# 19_2_Coupled_PP0_Top.net
KiCad netlist of a schematic drawn in Altium Designer
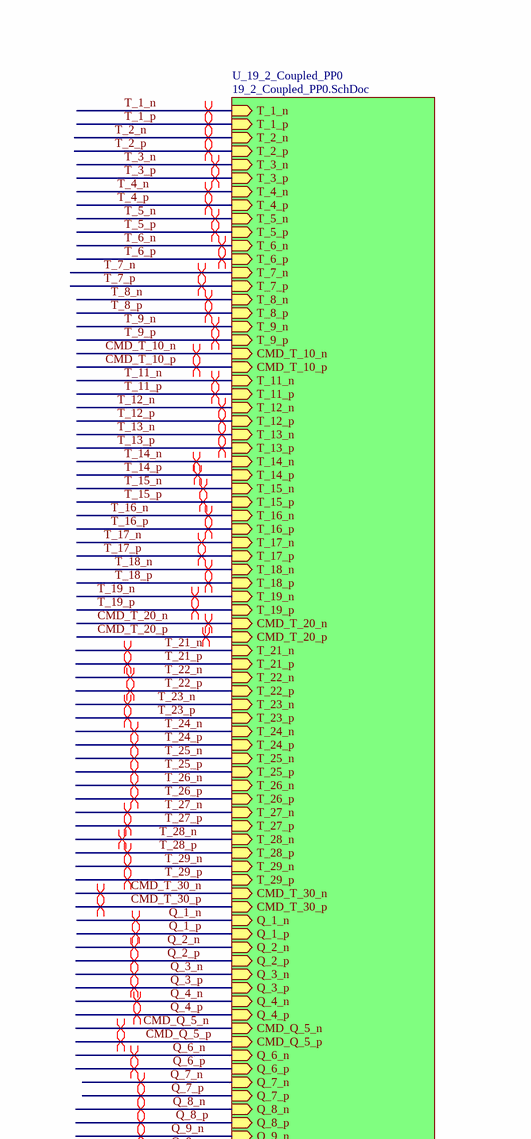
[diagram p0: 19_2_Coupled_PP0_Top.SchDoc, top left]
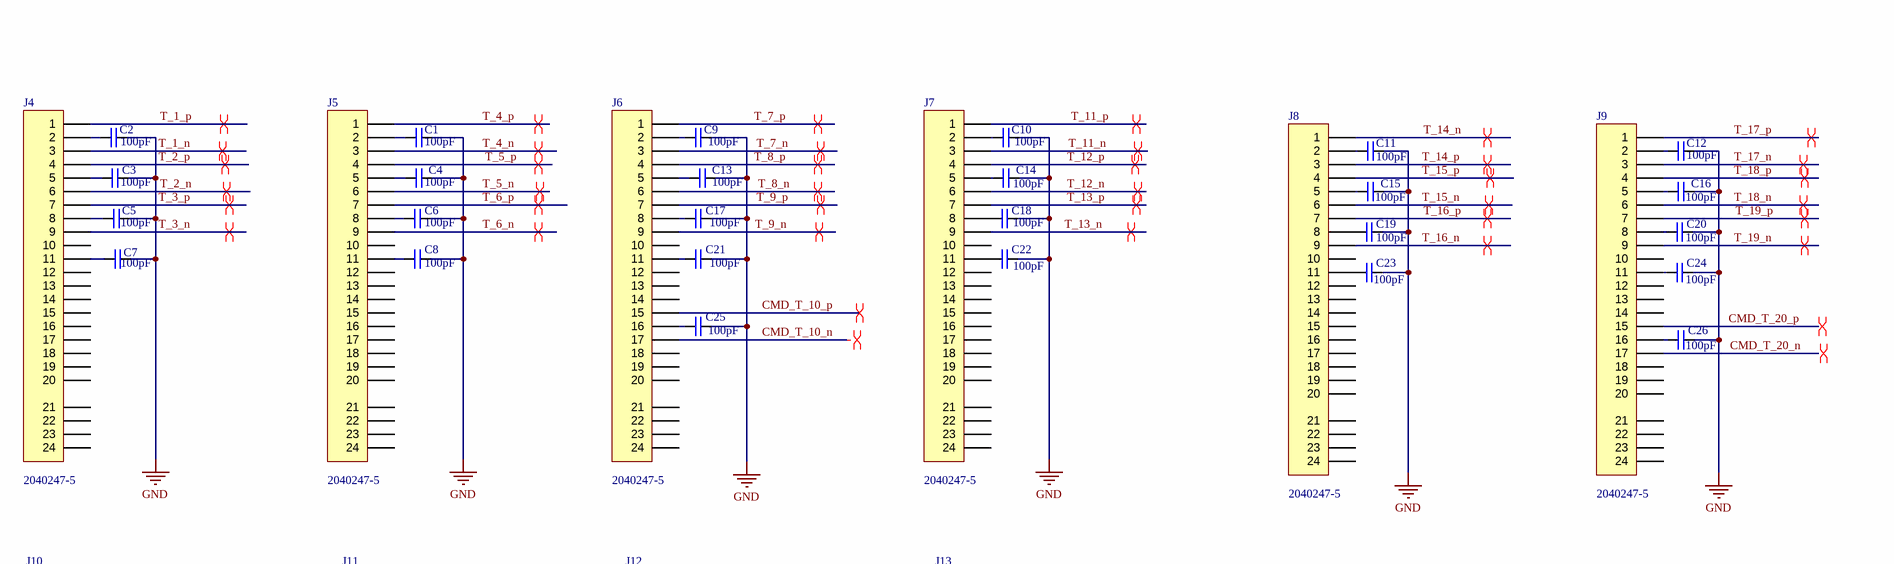
[diagram p1: 19_2_Coupled_PP0_Top.SchDoc, top right]
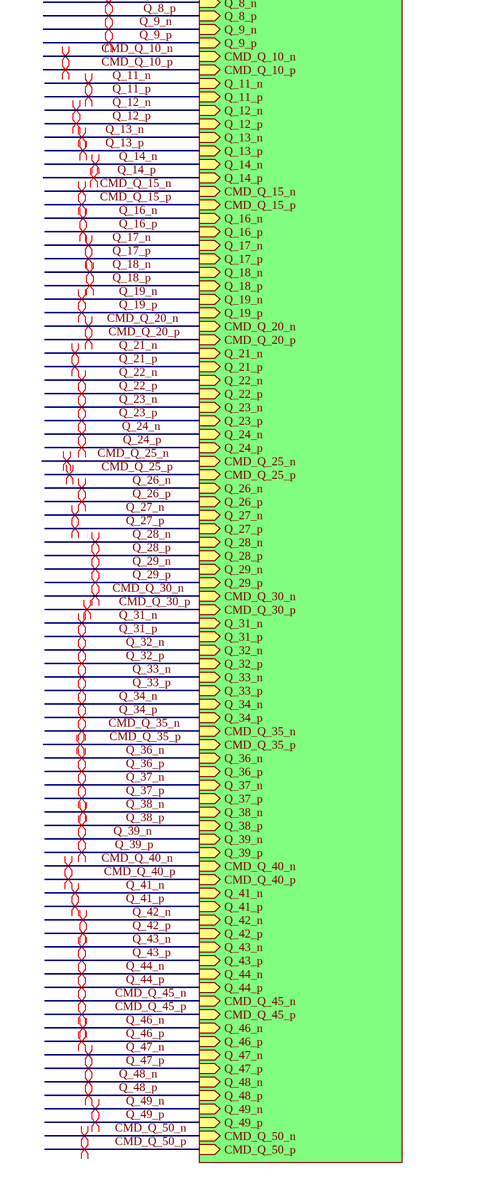
[diagram p2: 19_2_Coupled_PP0_Top.SchDoc, bottom left]
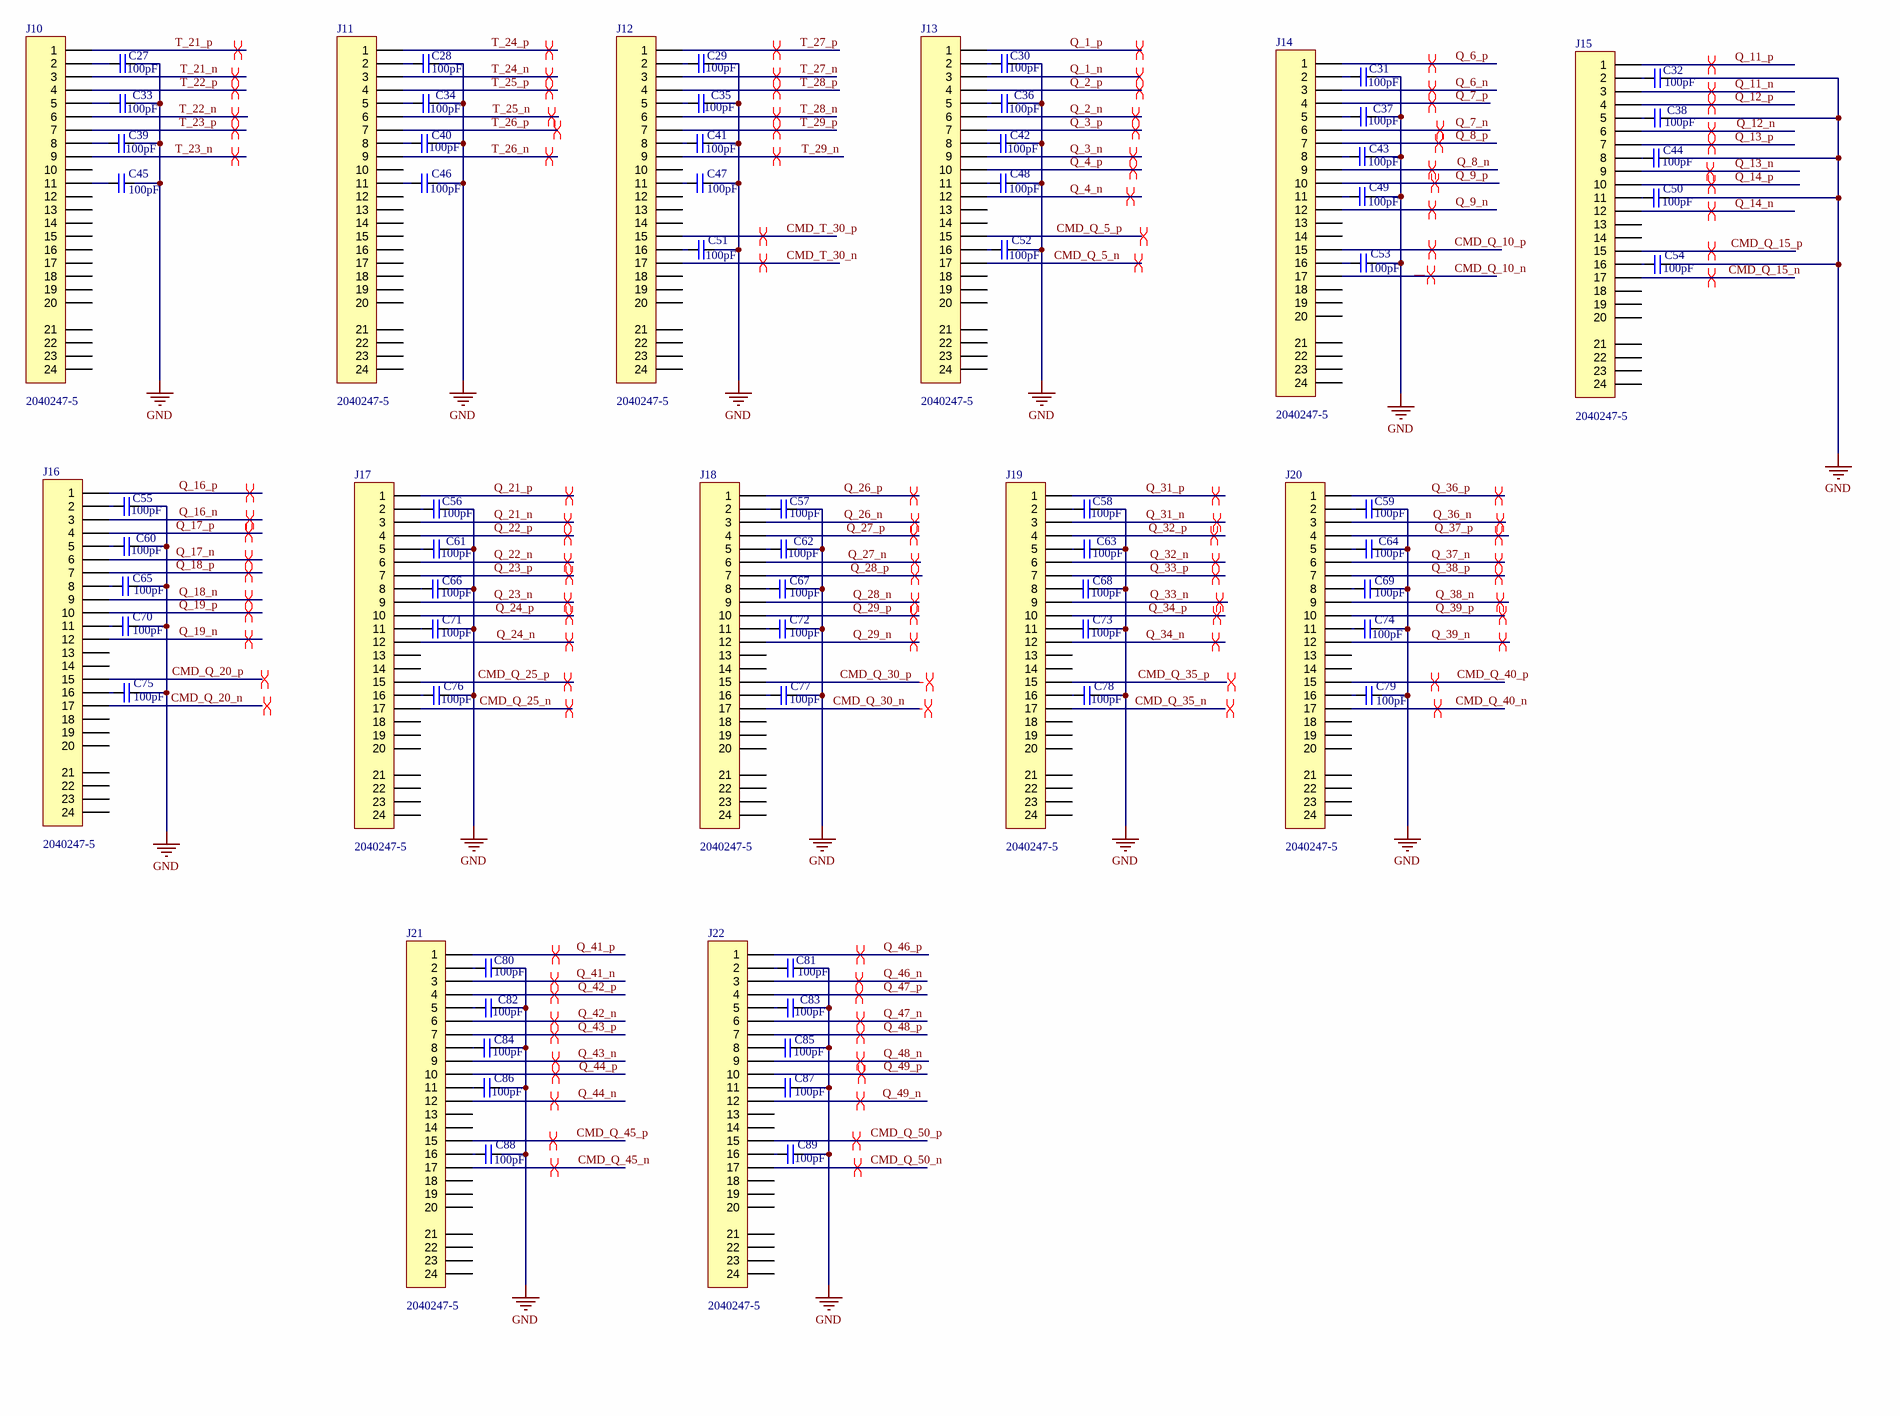
[diagram p3: 19_2_Coupled_PP0_Top.SchDoc, bottom right]

(export (version "E")
  (design (tool "Eeschema 10.0.6"))
  (components
    (comp (ref "C1")
      (value "100pF")
      (footprint "SM0201")
      (description "PPI, 0201N101JW500; CAP. 100pF 50V 5%, SM0201")
      (fields (field (name "MANUFACTURER") "PPI") (field (name "PARTNUMBER") "0201N101JW500"))
      (libsource (lib "yee_sch_lib") (part "C0201N101JW500"))
    )
    (comp (ref "C2")
      (value "100pF")
      (footprint "SM0201")
      (description "PPI, 0201N101JW500; CAP. 100pF 50V 5%, SM0201")
      (fields (field (name "MANUFACTURER") "PPI") (field (name "PARTNUMBER") "0201N101JW500"))
      (libsource (lib "yee_sch_lib") (part "C0201N101JW500"))
    )
    (comp (ref "C3")
      (value "100pF")
      (footprint "SM0201")
      (description "PPI, 0201N101JW500; CAP. 100pF 50V 5%, SM0201")
      (fields (field (name "MANUFACTURER") "PPI") (field (name "PARTNUMBER") "0201N101JW500"))
      (libsource (lib "yee_sch_lib") (part "C0201N101JW500"))
    )
    (comp (ref "C4")
      (value "100pF")
      (footprint "SM0201")
      (description "PPI, 0201N101JW500; CAP. 100pF 50V 5%, SM0201")
      (fields (field (name "MANUFACTURER") "PPI") (field (name "PARTNUMBER") "0201N101JW500"))
      (libsource (lib "yee_sch_lib") (part "C0201N101JW500"))
    )
    (comp (ref "C5")
      (value "100pF")
      (footprint "SM0201")
      (description "PPI, 0201N101JW500; CAP. 100pF 50V 5%, SM0201")
      (fields (field (name "MANUFACTURER") "PPI") (field (name "PARTNUMBER") "0201N101JW500"))
      (libsource (lib "yee_sch_lib") (part "C0201N101JW500"))
    )
    (comp (ref "C6")
      (value "100pF")
      (footprint "SM0201")
      (description "PPI, 0201N101JW500; CAP. 100pF 50V 5%, SM0201")
      (fields (field (name "MANUFACTURER") "PPI") (field (name "PARTNUMBER") "0201N101JW500"))
      (libsource (lib "yee_sch_lib") (part "C0201N101JW500"))
    )
    (comp (ref "C7")
      (value "100pF")
      (footprint "SM0201")
      (description "PPI, 0201N101JW500; CAP. 100pF 50V 5%, SM0201")
      (fields (field (name "MANUFACTURER") "PPI") (field (name "PARTNUMBER") "0201N101JW500"))
      (libsource (lib "yee_sch_lib") (part "C0201N101JW500"))
    )
    (comp (ref "C8")
      (value "100pF")
      (footprint "SM0201")
      (description "PPI, 0201N101JW500; CAP. 100pF 50V 5%, SM0201")
      (fields (field (name "MANUFACTURER") "PPI") (field (name "PARTNUMBER") "0201N101JW500"))
      (libsource (lib "yee_sch_lib") (part "C0201N101JW500"))
    )
    (comp (ref "C9")
      (value "100pF")
      (footprint "SM0201")
      (description "PPI, 0201N101JW500; CAP. 100pF 50V 5%, SM0201")
      (fields (field (name "MANUFACTURER") "PPI") (field (name "PARTNUMBER") "0201N101JW500"))
      (libsource (lib "yee_sch_lib") (part "C0201N101JW500"))
    )
    (comp (ref "C10")
      (value "100pF")
      (footprint "SM0201")
      (description "PPI, 0201N101JW500; CAP. 100pF 50V 5%, SM0201")
      (fields (field (name "MANUFACTURER") "PPI") (field (name "PARTNUMBER") "0201N101JW500"))
      (libsource (lib "yee_sch_lib") (part "C0201N101JW500"))
    )
    (comp (ref "C11")
      (value "100pF")
      (footprint "SM0201")
      (description "PPI, 0201N101JW500; CAP. 100pF 50V 5%, SM0201")
      (fields (field (name "MANUFACTURER") "PPI") (field (name "PARTNUMBER") "0201N101JW500"))
      (libsource (lib "yee_sch_lib") (part "C0201N101JW500"))
    )
    (comp (ref "C12")
      (value "100pF")
      (footprint "SM0201")
      (description "PPI, 0201N101JW500; CAP. 100pF 50V 5%, SM0201")
      (fields (field (name "MANUFACTURER") "PPI") (field (name "PARTNUMBER") "0201N101JW500"))
      (libsource (lib "yee_sch_lib") (part "C0201N101JW500"))
    )
    (comp (ref "C13")
      (value "100pF")
      (footprint "SM0201")
      (description "PPI, 0201N101JW500; CAP. 100pF 50V 5%, SM0201")
      (fields (field (name "MANUFACTURER") "PPI") (field (name "PARTNUMBER") "0201N101JW500"))
      (libsource (lib "yee_sch_lib") (part "C0201N101JW500"))
    )
    (comp (ref "C14")
      (value "100pF")
      (footprint "SM0201")
      (description "PPI, 0201N101JW500; CAP. 100pF 50V 5%, SM0201")
      (fields (field (name "MANUFACTURER") "PPI") (field (name "PARTNUMBER") "0201N101JW500"))
      (libsource (lib "yee_sch_lib") (part "C0201N101JW500"))
    )
    (comp (ref "C15")
      (value "100pF")
      (footprint "SM0201")
      (description "PPI, 0201N101JW500; CAP. 100pF 50V 5%, SM0201")
      (fields (field (name "MANUFACTURER") "PPI") (field (name "PARTNUMBER") "0201N101JW500"))
      (libsource (lib "yee_sch_lib") (part "C0201N101JW500"))
    )
    (comp (ref "C16")
      (value "100pF")
      (footprint "SM0201")
      (description "PPI, 0201N101JW500; CAP. 100pF 50V 5%, SM0201")
      (fields (field (name "MANUFACTURER") "PPI") (field (name "PARTNUMBER") "0201N101JW500"))
      (libsource (lib "yee_sch_lib") (part "C0201N101JW500"))
    )
    (comp (ref "C17")
      (value "100pF")
      (footprint "SM0201")
      (description "PPI, 0201N101JW500; CAP. 100pF 50V 5%, SM0201")
      (fields (field (name "MANUFACTURER") "PPI") (field (name "PARTNUMBER") "0201N101JW500"))
      (libsource (lib "yee_sch_lib") (part "C0201N101JW500"))
    )
    (comp (ref "C18")
      (value "100pF")
      (footprint "SM0201")
      (description "PPI, 0201N101JW500; CAP. 100pF 50V 5%, SM0201")
      (fields (field (name "MANUFACTURER") "PPI") (field (name "PARTNUMBER") "0201N101JW500"))
      (libsource (lib "yee_sch_lib") (part "C0201N101JW500"))
    )
    (comp (ref "C19")
      (value "100pF")
      (footprint "SM0201")
      (description "PPI, 0201N101JW500; CAP. 100pF 50V 5%, SM0201")
      (fields (field (name "MANUFACTURER") "PPI") (field (name "PARTNUMBER") "0201N101JW500"))
      (libsource (lib "yee_sch_lib") (part "C0201N101JW500"))
    )
    (comp (ref "C20")
      (value "100pF")
      (footprint "SM0201")
      (description "PPI, 0201N101JW500; CAP. 100pF 50V 5%, SM0201")
      (fields (field (name "MANUFACTURER") "PPI") (field (name "PARTNUMBER") "0201N101JW500"))
      (libsource (lib "yee_sch_lib") (part "C0201N101JW500"))
    )
    (comp (ref "C21")
      (value "100pF")
      (footprint "SM0201")
      (description "PPI, 0201N101JW500; CAP. 100pF 50V 5%, SM0201")
      (fields (field (name "MANUFACTURER") "PPI") (field (name "PARTNUMBER") "0201N101JW500"))
      (libsource (lib "yee_sch_lib") (part "C0201N101JW500"))
    )
    (comp (ref "C22")
      (value "100pF")
      (footprint "SM0201")
      (description "PPI, 0201N101JW500; CAP. 100pF 50V 5%, SM0201")
      (fields (field (name "MANUFACTURER") "PPI") (field (name "PARTNUMBER") "0201N101JW500"))
      (libsource (lib "yee_sch_lib") (part "C0201N101JW500"))
    )
    (comp (ref "C23")
      (value "100pF")
      (footprint "SM0201")
      (description "PPI, 0201N101JW500; CAP. 100pF 50V 5%, SM0201")
      (fields (field (name "MANUFACTURER") "PPI") (field (name "PARTNUMBER") "0201N101JW500"))
      (libsource (lib "yee_sch_lib") (part "C0201N101JW500"))
    )
    (comp (ref "C24")
      (value "100pF")
      (footprint "SM0201")
      (description "PPI, 0201N101JW500; CAP. 100pF 50V 5%, SM0201")
      (fields (field (name "MANUFACTURER") "PPI") (field (name "PARTNUMBER") "0201N101JW500"))
      (libsource (lib "yee_sch_lib") (part "C0201N101JW500"))
    )
    (comp (ref "C25")
      (value "100pF")
      (footprint "SM0201")
      (description "PPI, 0201N101JW500; CAP. 100pF 50V 5%, SM0201")
      (fields (field (name "MANUFACTURER") "PPI") (field (name "PARTNUMBER") "0201N101JW500"))
      (libsource (lib "yee_sch_lib") (part "C0201N101JW500"))
    )
    (comp (ref "C26")
      (value "100pF")
      (footprint "SM0201")
      (description "PPI, 0201N101JW500; CAP. 100pF 50V 5%, SM0201")
      (fields (field (name "MANUFACTURER") "PPI") (field (name "PARTNUMBER") "0201N101JW500"))
      (libsource (lib "yee_sch_lib") (part "C0201N101JW500"))
    )
    (comp (ref "C27")
      (value "100pF")
      (footprint "SM0201")
      (description "PPI, 0201N101JW500; CAP. 100pF 50V 5%, SM0201")
      (fields (field (name "MANUFACTURER") "PPI") (field (name "PARTNUMBER") "0201N101JW500"))
      (libsource (lib "yee_sch_lib") (part "C0201N101JW500"))
    )
    (comp (ref "C28")
      (value "100pF")
      (footprint "SM0201")
      (description "PPI, 0201N101JW500; CAP. 100pF 50V 5%, SM0201")
      (fields (field (name "MANUFACTURER") "PPI") (field (name "PARTNUMBER") "0201N101JW500"))
      (libsource (lib "yee_sch_lib") (part "C0201N101JW500"))
    )
    (comp (ref "C29")
      (value "100pF")
      (footprint "SM0201")
      (description "PPI, 0201N101JW500; CAP. 100pF 50V 5%, SM0201")
      (fields (field (name "MANUFACTURER") "PPI") (field (name "PARTNUMBER") "0201N101JW500"))
      (libsource (lib "yee_sch_lib") (part "C0201N101JW500"))
    )
    (comp (ref "C30")
      (value "100pF")
      (footprint "SM0201")
      (description "PPI, 0201N101JW500; CAP. 100pF 50V 5%, SM0201")
      (fields (field (name "MANUFACTURER") "PPI") (field (name "PARTNUMBER") "0201N101JW500"))
      (libsource (lib "yee_sch_lib") (part "C0201N101JW500"))
    )
    (comp (ref "C31")
      (value "100pF")
      (footprint "SM0201")
      (description "PPI, 0201N101JW500; CAP. 100pF 50V 5%, SM0201")
      (fields (field (name "MANUFACTURER") "PPI") (field (name "PARTNUMBER") "0201N101JW500"))
      (libsource (lib "yee_sch_lib") (part "C0201N101JW500"))
    )
    (comp (ref "C32")
      (value "100pF")
      (footprint "SM0201")
      (description "PPI, 0201N101JW500; CAP. 100pF 50V 5%, SM0201")
      (fields (field (name "MANUFACTURER") "PPI") (field (name "PARTNUMBER") "0201N101JW500"))
      (libsource (lib "yee_sch_lib") (part "C0201N101JW500"))
    )
    (comp (ref "C33")
      (value "100pF")
      (footprint "SM0201")
      (description "PPI, 0201N101JW500; CAP. 100pF 50V 5%, SM0201")
      (fields (field (name "MANUFACTURER") "PPI") (field (name "PARTNUMBER") "0201N101JW500"))
      (libsource (lib "yee_sch_lib") (part "C0201N101JW500"))
    )
    (comp (ref "C34")
      (value "100pF")
      (footprint "SM0201")
      (description "PPI, 0201N101JW500; CAP. 100pF 50V 5%, SM0201")
      (fields (field (name "MANUFACTURER") "PPI") (field (name "PARTNUMBER") "0201N101JW500"))
      (libsource (lib "yee_sch_lib") (part "C0201N101JW500"))
    )
    (comp (ref "C35")
      (value "100pF")
      (footprint "SM0201")
      (description "PPI, 0201N101JW500; CAP. 100pF 50V 5%, SM0201")
      (fields (field (name "MANUFACTURER") "PPI") (field (name "PARTNUMBER") "0201N101JW500"))
      (libsource (lib "yee_sch_lib") (part "C0201N101JW500"))
    )
    (comp (ref "C36")
      (value "100pF")
      (footprint "SM0201")
      (description "PPI, 0201N101JW500; CAP. 100pF 50V 5%, SM0201")
      (fields (field (name "MANUFACTURER") "PPI") (field (name "PARTNUMBER") "0201N101JW500"))
      (libsource (lib "yee_sch_lib") (part "C0201N101JW500"))
    )
    (comp (ref "C37")
      (value "100pF")
      (footprint "SM0201")
      (description "PPI, 0201N101JW500; CAP. 100pF 50V 5%, SM0201")
      (fields (field (name "MANUFACTURER") "PPI") (field (name "PARTNUMBER") "0201N101JW500"))
      (libsource (lib "yee_sch_lib") (part "C0201N101JW500"))
    )
    (comp (ref "C38")
      (value "100pF")
      (footprint "SM0201")
      (description "PPI, 0201N101JW500; CAP. 100pF 50V 5%, SM0201")
      (fields (field (name "MANUFACTURER") "PPI") (field (name "PARTNUMBER") "0201N101JW500"))
      (libsource (lib "yee_sch_lib") (part "C0201N101JW500"))
    )
    (comp (ref "C39")
      (value "100pF")
      (footprint "SM0201")
      (description "PPI, 0201N101JW500; CAP. 100pF 50V 5%, SM0201")
      (fields (field (name "MANUFACTURER") "PPI") (field (name "PARTNUMBER") "0201N101JW500"))
      (libsource (lib "yee_sch_lib") (part "C0201N101JW500"))
    )
    (comp (ref "C40")
      (value "100pF")
      (footprint "SM0201")
      (description "PPI, 0201N101JW500; CAP. 100pF 50V 5%, SM0201")
      (fields (field (name "MANUFACTURER") "PPI") (field (name "PARTNUMBER") "0201N101JW500"))
      (libsource (lib "yee_sch_lib") (part "C0201N101JW500"))
    )
    (comp (ref "C41")
      (value "100pF")
      (footprint "SM0201")
      (description "PPI, 0201N101JW500; CAP. 100pF 50V 5%, SM0201")
      (fields (field (name "MANUFACTURER") "PPI") (field (name "PARTNUMBER") "0201N101JW500"))
      (libsource (lib "yee_sch_lib") (part "C0201N101JW500"))
    )
    (comp (ref "C42")
      (value "100pF")
      (footprint "SM0201")
      (description "PPI, 0201N101JW500; CAP. 100pF 50V 5%, SM0201")
      (fields (field (name "MANUFACTURER") "PPI") (field (name "PARTNUMBER") "0201N101JW500"))
      (libsource (lib "yee_sch_lib") (part "C0201N101JW500"))
    )
    (comp (ref "C43")
      (value "100pF")
      (footprint "SM0201")
      (description "PPI, 0201N101JW500; CAP. 100pF 50V 5%, SM0201")
      (fields (field (name "MANUFACTURER") "PPI") (field (name "PARTNUMBER") "0201N101JW500"))
      (libsource (lib "yee_sch_lib") (part "C0201N101JW500"))
    )
    (comp (ref "C44")
      (value "100pF")
      (footprint "SM0201")
      (description "PPI, 0201N101JW500; CAP. 100pF 50V 5%, SM0201")
      (fields (field (name "MANUFACTURER") "PPI") (field (name "PARTNUMBER") "0201N101JW500"))
      (libsource (lib "yee_sch_lib") (part "C0201N101JW500"))
    )
    (comp (ref "C45")
      (value "100pF")
      (footprint "SM0201")
      (description "PPI, 0201N101JW500; CAP. 100pF 50V 5%, SM0201")
      (fields (field (name "MANUFACTURER") "PPI") (field (name "PARTNUMBER") "0201N101JW500"))
      (libsource (lib "yee_sch_lib") (part "C0201N101JW500"))
    )
    (comp (ref "C46")
      (value "100pF")
      (footprint "SM0201")
      (description "PPI, 0201N101JW500; CAP. 100pF 50V 5%, SM0201")
      (fields (field (name "MANUFACTURER") "PPI") (field (name "PARTNUMBER") "0201N101JW500"))
      (libsource (lib "yee_sch_lib") (part "C0201N101JW500"))
    )
    (comp (ref "C47")
      (value "100pF")
      (footprint "SM0201")
      (description "PPI, 0201N101JW500; CAP. 100pF 50V 5%, SM0201")
      (fields (field (name "MANUFACTURER") "PPI") (field (name "PARTNUMBER") "0201N101JW500"))
      (libsource (lib "yee_sch_lib") (part "C0201N101JW500"))
    )
    (comp (ref "C48")
      (value "100pF")
      (footprint "SM0201")
      (description "PPI, 0201N101JW500; CAP. 100pF 50V 5%, SM0201")
      (fields (field (name "MANUFACTURER") "PPI") (field (name "PARTNUMBER") "0201N101JW500"))
      (libsource (lib "yee_sch_lib") (part "C0201N101JW500"))
    )
    (comp (ref "C49")
      (value "100pF")
      (footprint "SM0201")
      (description "PPI, 0201N101JW500; CAP. 100pF 50V 5%, SM0201")
      (fields (field (name "MANUFACTURER") "PPI") (field (name "PARTNUMBER") "0201N101JW500"))
      (libsource (lib "yee_sch_lib") (part "C0201N101JW500"))
    )
    (comp (ref "C50")
      (value "100pF")
      (footprint "SM0201")
      (description "PPI, 0201N101JW500; CAP. 100pF 50V 5%, SM0201")
      (fields (field (name "MANUFACTURER") "PPI") (field (name "PARTNUMBER") "0201N101JW500"))
      (libsource (lib "yee_sch_lib") (part "C0201N101JW500"))
    )
    (comp (ref "C51")
      (value "100pF")
      (footprint "SM0201")
      (description "PPI, 0201N101JW500; CAP. 100pF 50V 5%, SM0201")
      (fields (field (name "MANUFACTURER") "PPI") (field (name "PARTNUMBER") "0201N101JW500"))
      (libsource (lib "yee_sch_lib") (part "C0201N101JW500"))
    )
    (comp (ref "C52")
      (value "100pF")
      (footprint "SM0201")
      (description "PPI, 0201N101JW500; CAP. 100pF 50V 5%, SM0201")
      (fields (field (name "MANUFACTURER") "PPI") (field (name "PARTNUMBER") "0201N101JW500"))
      (libsource (lib "yee_sch_lib") (part "C0201N101JW500"))
    )
    (comp (ref "C53")
      (value "100pF")
      (footprint "SM0201")
      (description "PPI, 0201N101JW500; CAP. 100pF 50V 5%, SM0201")
      (fields (field (name "MANUFACTURER") "PPI") (field (name "PARTNUMBER") "0201N101JW500"))
      (libsource (lib "yee_sch_lib") (part "C0201N101JW500"))
    )
    (comp (ref "C54")
      (value "100pF")
      (footprint "SM0201")
      (description "PPI, 0201N101JW500; CAP. 100pF 50V 5%, SM0201")
      (fields (field (name "MANUFACTURER") "PPI") (field (name "PARTNUMBER") "0201N101JW500"))
      (libsource (lib "yee_sch_lib") (part "C0201N101JW500"))
    )
    (comp (ref "C55")
      (value "100pF")
      (footprint "SM0201")
      (description "PPI, 0201N101JW500; CAP. 100pF 50V 5%, SM0201")
      (fields (field (name "MANUFACTURER") "PPI") (field (name "PARTNUMBER") "0201N101JW500"))
      (libsource (lib "yee_sch_lib") (part "C0201N101JW500"))
    )
    (comp (ref "C56")
      (value "100pF")
      (footprint "SM0201")
      (description "PPI, 0201N101JW500; CAP. 100pF 50V 5%, SM0201")
      (fields (field (name "MANUFACTURER") "PPI") (field (name "PARTNUMBER") "0201N101JW500"))
      (libsource (lib "yee_sch_lib") (part "C0201N101JW500"))
    )
    (comp (ref "C57")
      (value "100pF")
      (footprint "SM0201")
      (description "PPI, 0201N101JW500; CAP. 100pF 50V 5%, SM0201")
      (fields (field (name "MANUFACTURER") "PPI") (field (name "PARTNUMBER") "0201N101JW500"))
      (libsource (lib "yee_sch_lib") (part "C0201N101JW500"))
    )
    (comp (ref "C58")
      (value "100pF")
      (footprint "SM0201")
      (description "PPI, 0201N101JW500; CAP. 100pF 50V 5%, SM0201")
      (fields (field (name "MANUFACTURER") "PPI") (field (name "PARTNUMBER") "0201N101JW500"))
      (libsource (lib "yee_sch_lib") (part "C0201N101JW500"))
    )
    (comp (ref "C59")
      (value "100pF")
      (footprint "SM0201")
      (description "PPI, 0201N101JW500; CAP. 100pF 50V 5%, SM0201")
      (fields (field (name "MANUFACTURER") "PPI") (field (name "PARTNUMBER") "0201N101JW500"))
      (libsource (lib "yee_sch_lib") (part "C0201N101JW500"))
    )
    (comp (ref "C60")
      (value "100pF")
      (footprint "SM0201")
      (description "PPI, 0201N101JW500; CAP. 100pF 50V 5%, SM0201")
      (fields (field (name "MANUFACTURER") "PPI") (field (name "PARTNUMBER") "0201N101JW500"))
      (libsource (lib "yee_sch_lib") (part "C0201N101JW500"))
    )
    (comp (ref "C61")
      (value "100pF")
      (footprint "SM0201")
      (description "PPI, 0201N101JW500; CAP. 100pF 50V 5%, SM0201")
      (fields (field (name "MANUFACTURER") "PPI") (field (name "PARTNUMBER") "0201N101JW500"))
      (libsource (lib "yee_sch_lib") (part "C0201N101JW500"))
    )
    (comp (ref "C62")
      (value "100pF")
      (footprint "SM0201")
      (description "PPI, 0201N101JW500; CAP. 100pF 50V 5%, SM0201")
      (fields (field (name "MANUFACTURER") "PPI") (field (name "PARTNUMBER") "0201N101JW500"))
      (libsource (lib "yee_sch_lib") (part "C0201N101JW500"))
    )
    (comp (ref "C63")
      (value "100pF")
      (footprint "SM0201")
      (description "PPI, 0201N101JW500; CAP. 100pF 50V 5%, SM0201")
      (fields (field (name "MANUFACTURER") "PPI") (field (name "PARTNUMBER") "0201N101JW500"))
      (libsource (lib "yee_sch_lib") (part "C0201N101JW500"))
    )
    (comp (ref "C64")
      (value "100pF")
      (footprint "SM0201")
      (description "PPI, 0201N101JW500; CAP. 100pF 50V 5%, SM0201")
      (fields (field (name "MANUFACTURER") "PPI") (field (name "PARTNUMBER") "0201N101JW500"))
      (libsource (lib "yee_sch_lib") (part "C0201N101JW500"))
    )
    (comp (ref "C65")
      (value "100pF")
      (footprint "SM0201")
      (description "PPI, 0201N101JW500; CAP. 100pF 50V 5%, SM0201")
      (fields (field (name "MANUFACTURER") "PPI") (field (name "PARTNUMBER") "0201N101JW500"))
      (libsource (lib "yee_sch_lib") (part "C0201N101JW500"))
    )
    (comp (ref "C66")
      (value "100pF")
      (footprint "SM0201")
      (description "PPI, 0201N101JW500; CAP. 100pF 50V 5%, SM0201")
      (fields (field (name "MANUFACTURER") "PPI") (field (name "PARTNUMBER") "0201N101JW500"))
      (libsource (lib "yee_sch_lib") (part "C0201N101JW500"))
    )
    (comp (ref "C67")
      (value "100pF")
      (footprint "SM0201")
      (description "PPI, 0201N101JW500; CAP. 100pF 50V 5%, SM0201")
      (fields (field (name "MANUFACTURER") "PPI") (field (name "PARTNUMBER") "0201N101JW500"))
      (libsource (lib "yee_sch_lib") (part "C0201N101JW500"))
    )
    (comp (ref "C68")
      (value "100pF")
      (footprint "SM0201")
      (description "PPI, 0201N101JW500; CAP. 100pF 50V 5%, SM0201")
      (fields (field (name "MANUFACTURER") "PPI") (field (name "PARTNUMBER") "0201N101JW500"))
      (libsource (lib "yee_sch_lib") (part "C0201N101JW500"))
    )
    (comp (ref "C69")
      (value "100pF")
      (footprint "SM0201")
      (description "PPI, 0201N101JW500; CAP. 100pF 50V 5%, SM0201")
      (fields (field (name "MANUFACTURER") "PPI") (field (name "PARTNUMBER") "0201N101JW500"))
      (libsource (lib "yee_sch_lib") (part "C0201N101JW500"))
    )
    (comp (ref "C70")
      (value "100pF")
      (footprint "SM0201")
      (description "PPI, 0201N101JW500; CAP. 100pF 50V 5%, SM0201")
      (fields (field (name "MANUFACTURER") "PPI") (field (name "PARTNUMBER") "0201N101JW500"))
      (libsource (lib "yee_sch_lib") (part "C0201N101JW500"))
    )
    (comp (ref "C71")
      (value "100pF")
      (footprint "SM0201")
      (description "PPI, 0201N101JW500; CAP. 100pF 50V 5%, SM0201")
      (fields (field (name "MANUFACTURER") "PPI") (field (name "PARTNUMBER") "0201N101JW500"))
      (libsource (lib "yee_sch_lib") (part "C0201N101JW500"))
    )
    (comp (ref "C72")
      (value "100pF")
      (footprint "SM0201")
      (description "PPI, 0201N101JW500; CAP. 100pF 50V 5%, SM0201")
      (fields (field (name "MANUFACTURER") "PPI") (field (name "PARTNUMBER") "0201N101JW500"))
      (libsource (lib "yee_sch_lib") (part "C0201N101JW500"))
    )
    (comp (ref "C73")
      (value "100pF")
      (footprint "SM0201")
      (description "PPI, 0201N101JW500; CAP. 100pF 50V 5%, SM0201")
      (fields (field (name "MANUFACTURER") "PPI") (field (name "PARTNUMBER") "0201N101JW500"))
      (libsource (lib "yee_sch_lib") (part "C0201N101JW500"))
    )
    (comp (ref "C74")
      (value "100pF")
      (footprint "SM0201")
      (description "PPI, 0201N101JW500; CAP. 100pF 50V 5%, SM0201")
      (fields (field (name "MANUFACTURER") "PPI") (field (name "PARTNUMBER") "0201N101JW500"))
      (libsource (lib "yee_sch_lib") (part "C0201N101JW500"))
    )
    (comp (ref "C75")
      (value "100pF")
      (footprint "SM0201")
      (description "PPI, 0201N101JW500; CAP. 100pF 50V 5%, SM0201")
      (fields (field (name "MANUFACTURER") "PPI") (field (name "PARTNUMBER") "0201N101JW500"))
      (libsource (lib "yee_sch_lib") (part "C0201N101JW500"))
    )
    (comp (ref "C76")
      (value "100pF")
      (footprint "SM0201")
      (description "PPI, 0201N101JW500; CAP. 100pF 50V 5%, SM0201")
      (fields (field (name "MANUFACTURER") "PPI") (field (name "PARTNUMBER") "0201N101JW500"))
      (libsource (lib "yee_sch_lib") (part "C0201N101JW500"))
    )
    (comp (ref "C77")
      (value "100pF")
      (footprint "SM0201")
      (description "PPI, 0201N101JW500; CAP. 100pF 50V 5%, SM0201")
      (fields (field (name "MANUFACTURER") "PPI") (field (name "PARTNUMBER") "0201N101JW500"))
      (libsource (lib "yee_sch_lib") (part "C0201N101JW500"))
    )
    (comp (ref "C78")
      (value "100pF")
      (footprint "SM0201")
      (description "PPI, 0201N101JW500; CAP. 100pF 50V 5%, SM0201")
      (fields (field (name "MANUFACTURER") "PPI") (field (name "PARTNUMBER") "0201N101JW500"))
      (libsource (lib "yee_sch_lib") (part "C0201N101JW500"))
    )
    (comp (ref "C79")
      (value "100pF")
      (footprint "SM0201")
      (description "PPI, 0201N101JW500; CAP. 100pF 50V 5%, SM0201")
      (fields (field (name "MANUFACTURER") "PPI") (field (name "PARTNUMBER") "0201N101JW500"))
      (libsource (lib "yee_sch_lib") (part "C0201N101JW500"))
    )
    (comp (ref "C80")
      (value "100pF")
      (footprint "SM0201")
      (description "PPI, 0201N101JW500; CAP. 100pF 50V 5%, SM0201")
      (fields (field (name "MANUFACTURER") "PPI") (field (name "PARTNUMBER") "0201N101JW500"))
      (libsource (lib "yee_sch_lib") (part "C0201N101JW500"))
    )
    (comp (ref "C81")
      (value "100pF")
      (footprint "SM0201")
      (description "PPI, 0201N101JW500; CAP. 100pF 50V 5%, SM0201")
      (fields (field (name "MANUFACTURER") "PPI") (field (name "PARTNUMBER") "0201N101JW500"))
      (libsource (lib "yee_sch_lib") (part "C0201N101JW500"))
    )
    (comp (ref "C82")
      (value "100pF")
      (footprint "SM0201")
      (description "PPI, 0201N101JW500; CAP. 100pF 50V 5%, SM0201")
      (fields (field (name "MANUFACTURER") "PPI") (field (name "PARTNUMBER") "0201N101JW500"))
      (libsource (lib "yee_sch_lib") (part "C0201N101JW500"))
    )
    (comp (ref "C83")
      (value "100pF")
      (footprint "SM0201")
      (description "PPI, 0201N101JW500; CAP. 100pF 50V 5%, SM0201")
      (fields (field (name "MANUFACTURER") "PPI") (field (name "PARTNUMBER") "0201N101JW500"))
      (libsource (lib "yee_sch_lib") (part "C0201N101JW500"))
    )
    (comp (ref "C84")
      (value "100pF")
      (footprint "SM0201")
      (description "PPI, 0201N101JW500; CAP. 100pF 50V 5%, SM0201")
      (fields (field (name "MANUFACTURER") "PPI") (field (name "PARTNUMBER") "0201N101JW500"))
      (libsource (lib "yee_sch_lib") (part "C0201N101JW500"))
    )
    (comp (ref "C85")
      (value "100pF")
      (footprint "SM0201")
      (description "PPI, 0201N101JW500; CAP. 100pF 50V 5%, SM0201")
      (fields (field (name "MANUFACTURER") "PPI") (field (name "PARTNUMBER") "0201N101JW500"))
      (libsource (lib "yee_sch_lib") (part "C0201N101JW500"))
    )
    (comp (ref "C86")
      (value "100pF")
      (footprint "SM0201")
      (description "PPI, 0201N101JW500; CAP. 100pF 50V 5%, SM0201")
      (fields (field (name "MANUFACTURER") "PPI") (field (name "PARTNUMBER") "0201N101JW500"))
      (libsource (lib "yee_sch_lib") (part "C0201N101JW500"))
    )
    (comp (ref "C87")
      (value "100pF")
      (footprint "SM0201")
      (description "PPI, 0201N101JW500; CAP. 100pF 50V 5%, SM0201")
      (fields (field (name "MANUFACTURER") "PPI") (field (name "PARTNUMBER") "0201N101JW500"))
      (libsource (lib "yee_sch_lib") (part "C0201N101JW500"))
    )
    (comp (ref "C88")
      (value "100pF")
      (footprint "SM0201")
      (description "PPI, 0201N101JW500; CAP. 100pF 50V 5%, SM0201")
      (fields (field (name "MANUFACTURER") "PPI") (field (name "PARTNUMBER") "0201N101JW500"))
      (libsource (lib "yee_sch_lib") (part "C0201N101JW500"))
    )
    (comp (ref "C89")
      (value "100pF")
      (footprint "SM0201")
      (description "PPI, 0201N101JW500; CAP. 100pF 50V 5%, SM0201")
      (fields (field (name "MANUFACTURER") "PPI") (field (name "PARTNUMBER") "0201N101JW500"))
      (libsource (lib "yee_sch_lib") (part "C0201N101JW500"))
    )
    (comp (ref "J4")
      (value "2040247-5")
      (footprint "Tyco_2040247-5")
      (description "Tyco; 2040247-5, Display Port Right Angle SMT, Tyco_2040247-5")
      (fields (field (name "MANUFACTURER") "TYCO") (field (name "MANUFACTURER PART NUMBER") "2040247-5"))
      (libsource (lib "yee_sch_lib") (part "Tyco_2040247-5"))
    )
    (comp (ref "J5")
      (value "2040247-5")
      (footprint "Tyco_2040247-5")
      (description "Tyco; 2040247-5, Display Port Right Angle SMT, Tyco_2040247-5")
      (fields (field (name "MANUFACTURER") "TYCO") (field (name "MANUFACTURER PART NUMBER") "2040247-5"))
      (libsource (lib "yee_sch_lib") (part "Tyco_2040247-5"))
    )
    (comp (ref "J6")
      (value "2040247-5")
      (footprint "Tyco_2040247-5")
      (description "Tyco; 2040247-5, Display Port Right Angle SMT, Tyco_2040247-5")
      (fields (field (name "MANUFACTURER") "TYCO") (field (name "MANUFACTURER PART NUMBER") "2040247-5"))
      (libsource (lib "yee_sch_lib") (part "Tyco_2040247-5"))
    )
    (comp (ref "J7")
      (value "2040247-5")
      (footprint "Tyco_2040247-5")
      (description "Tyco; 2040247-5, Display Port Right Angle SMT, Tyco_2040247-5")
      (fields (field (name "MANUFACTURER") "TYCO") (field (name "MANUFACTURER PART NUMBER") "2040247-5"))
      (libsource (lib "yee_sch_lib") (part "Tyco_2040247-5"))
    )
    (comp (ref "J8")
      (value "2040247-5")
      (footprint "Tyco_2040247-5")
      (description "Tyco; 2040247-5, Display Port Right Angle SMT, Tyco_2040247-5")
      (fields (field (name "MANUFACTURER") "TYCO") (field (name "MANUFACTURER PART NUMBER") "2040247-5"))
      (libsource (lib "yee_sch_lib") (part "Tyco_2040247-5"))
    )
    (comp (ref "J9")
      (value "2040247-5")
      (footprint "Tyco_2040247-5")
      (description "Tyco; 2040247-5, Display Port Right Angle SMT, Tyco_2040247-5")
      (fields (field (name "MANUFACTURER") "TYCO") (field (name "MANUFACTURER PART NUMBER") "2040247-5"))
      (libsource (lib "yee_sch_lib") (part "Tyco_2040247-5"))
    )
    (comp (ref "J10")
      (value "2040247-5")
      (footprint "Tyco_2040247-5")
      (description "Tyco; 2040247-5, Display Port Right Angle SMT, Tyco_2040247-5")
      (fields (field (name "MANUFACTURER") "TYCO") (field (name "MANUFACTURER PART NUMBER") "2040247-5"))
      (libsource (lib "yee_sch_lib") (part "Tyco_2040247-5"))
    )
    (comp (ref "J11")
      (value "2040247-5")
      (footprint "Tyco_2040247-5")
      (description "Tyco; 2040247-5, Display Port Right Angle SMT, Tyco_2040247-5")
      (fields (field (name "MANUFACTURER") "TYCO") (field (name "MANUFACTURER PART NUMBER") "2040247-5"))
      (libsource (lib "yee_sch_lib") (part "Tyco_2040247-5"))
    )
    (comp (ref "J12")
      (value "2040247-5")
      (footprint "Tyco_2040247-5")
      (description "Tyco; 2040247-5, Display Port Right Angle SMT, Tyco_2040247-5")
      (fields (field (name "MANUFACTURER") "TYCO") (field (name "MANUFACTURER PART NUMBER") "2040247-5"))
      (libsource (lib "yee_sch_lib") (part "Tyco_2040247-5"))
    )
    (comp (ref "J13")
      (value "2040247-5")
      (footprint "Tyco_2040247-5")
      (description "Tyco; 2040247-5, Display Port Right Angle SMT, Tyco_2040247-5")
      (fields (field (name "MANUFACTURER") "TYCO") (field (name "MANUFACTURER PART NUMBER") "2040247-5"))
      (libsource (lib "yee_sch_lib") (part "Tyco_2040247-5"))
    )
    (comp (ref "J14")
      (value "2040247-5")
      (footprint "Tyco_2040247-5")
      (description "Tyco; 2040247-5, Display Port Right Angle SMT, Tyco_2040247-5")
      (fields (field (name "MANUFACTURER") "TYCO") (field (name "MANUFACTURER PART NUMBER") "2040247-5"))
      (libsource (lib "yee_sch_lib") (part "Tyco_2040247-5"))
    )
    (comp (ref "J15")
      (value "2040247-5")
      (footprint "Tyco_2040247-5")
      (description "Tyco; 2040247-5, Display Port Right Angle SMT, Tyco_2040247-5")
      (fields (field (name "MANUFACTURER") "TYCO") (field (name "MANUFACTURER PART NUMBER") "2040247-5"))
      (libsource (lib "yee_sch_lib") (part "Tyco_2040247-5"))
    )
    (comp (ref "J16")
      (value "2040247-5")
      (footprint "Tyco_2040247-5")
      (description "Tyco; 2040247-5, Display Port Right Angle SMT, Tyco_2040247-5")
      (fields (field (name "MANUFACTURER") "TYCO") (field (name "MANUFACTURER PART NUMBER") "2040247-5"))
      (libsource (lib "yee_sch_lib") (part "Tyco_2040247-5"))
    )
    (comp (ref "J17")
      (value "2040247-5")
      (footprint "Tyco_2040247-5")
      (description "Tyco; 2040247-5, Display Port Right Angle SMT, Tyco_2040247-5")
      (fields (field (name "MANUFACTURER") "TYCO") (field (name "MANUFACTURER PART NUMBER") "2040247-5"))
      (libsource (lib "yee_sch_lib") (part "Tyco_2040247-5"))
    )
    (comp (ref "J18")
      (value "2040247-5")
      (footprint "Tyco_2040247-5")
      (description "Tyco; 2040247-5, Display Port Right Angle SMT, Tyco_2040247-5")
      (fields (field (name "MANUFACTURER") "TYCO") (field (name "MANUFACTURER PART NUMBER") "2040247-5"))
      (libsource (lib "yee_sch_lib") (part "Tyco_2040247-5"))
    )
    (comp (ref "J19")
      (value "2040247-5")
      (footprint "Tyco_2040247-5")
      (description "Tyco; 2040247-5, Display Port Right Angle SMT, Tyco_2040247-5")
      (fields (field (name "MANUFACTURER") "TYCO") (field (name "MANUFACTURER PART NUMBER") "2040247-5"))
      (libsource (lib "yee_sch_lib") (part "Tyco_2040247-5"))
    )
    (comp (ref "J20")
      (value "2040247-5")
      (footprint "Tyco_2040247-5")
      (description "Tyco; 2040247-5, Display Port Right Angle SMT, Tyco_2040247-5")
      (fields (field (name "MANUFACTURER") "TYCO") (field (name "MANUFACTURER PART NUMBER") "2040247-5"))
      (libsource (lib "yee_sch_lib") (part "Tyco_2040247-5"))
    )
    (comp (ref "J21")
      (value "2040247-5")
      (footprint "Tyco_2040247-5")
      (description "Tyco; 2040247-5, Display Port Right Angle SMT, Tyco_2040247-5")
      (fields (field (name "MANUFACTURER") "TYCO") (field (name "MANUFACTURER PART NUMBER") "2040247-5"))
      (libsource (lib "yee_sch_lib") (part "Tyco_2040247-5"))
    )
    (comp (ref "J22")
      (value "2040247-5")
      (footprint "Tyco_2040247-5")
      (description "Tyco; 2040247-5, Display Port Right Angle SMT, Tyco_2040247-5")
      (fields (field (name "MANUFACTURER") "TYCO") (field (name "MANUFACTURER PART NUMBER") "2040247-5"))
      (libsource (lib "yee_sch_lib") (part "Tyco_2040247-5"))
    )
  )
  (nets
    (net (code "1") (name "/CMD_Q_5_n") (class "Default")
      (node (ref "J13") (pin "17") (pinfunction "17_17") (pintype "passive"))
    )
    (net (code "2") (name "/CMD_Q_5_p") (class "Default")
      (node (ref "J13") (pin "15") (pinfunction "15_15") (pintype "passive"))
    )
    (net (code "3") (name "/CMD_Q_10_n") (class "Default")
      (node (ref "J14") (pin "17") (pinfunction "17_17") (pintype "passive"))
    )
    (net (code "4") (name "/CMD_Q_10_p") (class "Default")
      (node (ref "J14") (pin "15") (pinfunction "15_15") (pintype "passive"))
    )
    (net (code "5") (name "/CMD_Q_15_n") (class "Default")
      (node (ref "J15") (pin "17") (pinfunction "17_17") (pintype "passive"))
    )
    (net (code "6") (name "/CMD_Q_15_p") (class "Default")
      (node (ref "J15") (pin "15") (pinfunction "15_15") (pintype "passive"))
    )
    (net (code "7") (name "/CMD_Q_20_n") (class "Default")
      (node (ref "J16") (pin "17") (pinfunction "17_17") (pintype "passive"))
    )
    (net (code "8") (name "/CMD_Q_20_p") (class "Default")
      (node (ref "J16") (pin "15") (pinfunction "15_15") (pintype "passive"))
    )
    (net (code "9") (name "/CMD_Q_25_n") (class "Default")
      (node (ref "J17") (pin "17") (pinfunction "17_17") (pintype "passive"))
    )
    (net (code "10") (name "/CMD_Q_25_p") (class "Default")
      (node (ref "J17") (pin "15") (pinfunction "15_15") (pintype "passive"))
    )
    (net (code "11") (name "/CMD_Q_30_n") (class "Default")
      (node (ref "J18") (pin "17") (pinfunction "17_17") (pintype "passive"))
    )
    (net (code "12") (name "/CMD_Q_30_p") (class "Default")
      (node (ref "J18") (pin "15") (pinfunction "15_15") (pintype "passive"))
    )
    (net (code "13") (name "/CMD_Q_35_n") (class "Default")
      (node (ref "J19") (pin "17") (pinfunction "17_17") (pintype "passive"))
    )
    (net (code "14") (name "/CMD_Q_35_p") (class "Default")
      (node (ref "J19") (pin "15") (pinfunction "15_15") (pintype "passive"))
    )
    (net (code "15") (name "/CMD_Q_40_n") (class "Default")
      (node (ref "J20") (pin "17") (pinfunction "17_17") (pintype "passive"))
    )
    (net (code "16") (name "/CMD_Q_40_p") (class "Default")
      (node (ref "J20") (pin "15") (pinfunction "15_15") (pintype "passive"))
    )
    (net (code "17") (name "/CMD_Q_45_n") (class "Default")
      (node (ref "J21") (pin "17") (pinfunction "17_17") (pintype "passive"))
    )
    (net (code "18") (name "/CMD_Q_45_p") (class "Default")
      (node (ref "J21") (pin "15") (pinfunction "15_15") (pintype "passive"))
    )
    (net (code "19") (name "/CMD_Q_50_n") (class "Default")
      (node (ref "J22") (pin "17") (pinfunction "17_17") (pintype "passive"))
    )
    (net (code "20") (name "/CMD_Q_50_p") (class "Default")
      (node (ref "J22") (pin "15") (pinfunction "15_15") (pintype "passive"))
    )
    (net (code "21") (name "/CMD_T_10_n") (class "Default")
      (node (ref "J6") (pin "17") (pinfunction "17_17") (pintype "passive"))
    )
    (net (code "22") (name "/CMD_T_10_p") (class "Default")
      (node (ref "J6") (pin "15") (pinfunction "15_15") (pintype "passive"))
    )
    (net (code "23") (name "/CMD_T_20_n") (class "Default")
      (node (ref "J9") (pin "17") (pinfunction "17_17") (pintype "passive"))
    )
    (net (code "24") (name "/CMD_T_20_p") (class "Default")
      (node (ref "J9") (pin "15") (pinfunction "15_15") (pintype "passive"))
    )
    (net (code "25") (name "/CMD_T_30_n") (class "Default")
      (node (ref "J12") (pin "17") (pinfunction "17_17") (pintype "passive"))
    )
    (net (code "26") (name "/CMD_T_30_p") (class "Default")
      (node (ref "J12") (pin "15") (pinfunction "15_15") (pintype "passive"))
    )
    (net (code "27") (name "/Q_1_n") (class "Default")
      (node (ref "J13") (pin "3") (pinfunction "3_3") (pintype "passive"))
    )
    (net (code "28") (name "/Q_1_p") (class "Default")
      (node (ref "J13") (pin "1") (pinfunction "1_1") (pintype "passive"))
    )
    (net (code "29") (name "/Q_2_n") (class "Default")
      (node (ref "J13") (pin "6") (pinfunction "6_6") (pintype "passive"))
    )
    (net (code "30") (name "/Q_2_p") (class "Default")
      (node (ref "J13") (pin "4") (pinfunction "4_4") (pintype "passive"))
    )
    (net (code "31") (name "/Q_3_n") (class "Default")
      (node (ref "J13") (pin "9") (pinfunction "9_9") (pintype "passive"))
    )
    (net (code "32") (name "/Q_3_p") (class "Default")
      (node (ref "J13") (pin "7") (pinfunction "7_7") (pintype "passive"))
    )
    (net (code "33") (name "/Q_4_n") (class "Default")
      (node (ref "J13") (pin "12") (pinfunction "12_12") (pintype "passive"))
    )
    (net (code "34") (name "/Q_4_p") (class "Default")
      (node (ref "J13") (pin "10") (pinfunction "10_10") (pintype "passive"))
    )
    (net (code "35") (name "/Q_6_n") (class "Default")
      (node (ref "J14") (pin "3") (pinfunction "3_3") (pintype "passive"))
    )
    (net (code "36") (name "/Q_6_p") (class "Default")
      (node (ref "J14") (pin "1") (pinfunction "1_1") (pintype "passive"))
    )
    (net (code "37") (name "/Q_7_n") (class "Default")
      (node (ref "J14") (pin "6") (pinfunction "6_6") (pintype "passive"))
    )
    (net (code "38") (name "/Q_7_p") (class "Default")
      (node (ref "J14") (pin "4") (pinfunction "4_4") (pintype "passive"))
    )
    (net (code "39") (name "/Q_8_n") (class "Default")
      (node (ref "J14") (pin "9") (pinfunction "9_9") (pintype "passive"))
    )
    (net (code "40") (name "/Q_8_p") (class "Default")
      (node (ref "J14") (pin "7") (pinfunction "7_7") (pintype "passive"))
    )
    (net (code "41") (name "/Q_9_n") (class "Default")
      (node (ref "J14") (pin "12") (pinfunction "12_12") (pintype "passive"))
    )
    (net (code "42") (name "/Q_9_p") (class "Default")
      (node (ref "J14") (pin "10") (pinfunction "10_10") (pintype "passive"))
    )
    (net (code "43") (name "/Q_11_n") (class "Default")
      (node (ref "J15") (pin "3") (pinfunction "3_3") (pintype "passive"))
    )
    (net (code "44") (name "/Q_11_p") (class "Default")
      (node (ref "J15") (pin "1") (pinfunction "1_1") (pintype "passive"))
    )
    (net (code "45") (name "/Q_12_n") (class "Default")
      (node (ref "J15") (pin "6") (pinfunction "6_6") (pintype "passive"))
    )
    (net (code "46") (name "/Q_12_p") (class "Default")
      (node (ref "J15") (pin "4") (pinfunction "4_4") (pintype "passive"))
    )
    (net (code "47") (name "/Q_13_n") (class "Default")
      (node (ref "J15") (pin "9") (pinfunction "9_9") (pintype "passive"))
    )
    (net (code "48") (name "/Q_13_p") (class "Default")
      (node (ref "J15") (pin "7") (pinfunction "7_7") (pintype "passive"))
    )
    (net (code "49") (name "/Q_14_n") (class "Default")
      (node (ref "J15") (pin "12") (pinfunction "12_12") (pintype "passive"))
    )
    (net (code "50") (name "/Q_14_p") (class "Default")
      (node (ref "J15") (pin "10") (pinfunction "10_10") (pintype "passive"))
    )
    (net (code "51") (name "/Q_16_n") (class "Default")
      (node (ref "J16") (pin "3") (pinfunction "3_3") (pintype "passive"))
    )
    (net (code "52") (name "/Q_16_p") (class "Default")
      (node (ref "J16") (pin "1") (pinfunction "1_1") (pintype "passive"))
    )
    (net (code "53") (name "/Q_17_n") (class "Default")
      (node (ref "J16") (pin "6") (pinfunction "6_6") (pintype "passive"))
    )
    (net (code "54") (name "/Q_17_p") (class "Default")
      (node (ref "J16") (pin "4") (pinfunction "4_4") (pintype "passive"))
    )
    (net (code "55") (name "/Q_18_n") (class "Default")
      (node (ref "J16") (pin "9") (pinfunction "9_9") (pintype "passive"))
    )
    (net (code "56") (name "/Q_18_p") (class "Default")
      (node (ref "J16") (pin "7") (pinfunction "7_7") (pintype "passive"))
    )
    (net (code "57") (name "/Q_19_n") (class "Default")
      (node (ref "J16") (pin "12") (pinfunction "12_12") (pintype "passive"))
    )
    (net (code "58") (name "/Q_19_p") (class "Default")
      (node (ref "J16") (pin "10") (pinfunction "10_10") (pintype "passive"))
    )
    (net (code "59") (name "/Q_21_n") (class "Default")
      (node (ref "J17") (pin "3") (pinfunction "3_3") (pintype "passive"))
    )
    (net (code "60") (name "/Q_21_p") (class "Default")
      (node (ref "J17") (pin "1") (pinfunction "1_1") (pintype "passive"))
    )
    (net (code "61") (name "/Q_22_n") (class "Default")
      (node (ref "J17") (pin "6") (pinfunction "6_6") (pintype "passive"))
    )
    (net (code "62") (name "/Q_22_p") (class "Default")
      (node (ref "J17") (pin "4") (pinfunction "4_4") (pintype "passive"))
    )
    (net (code "63") (name "/Q_23_n") (class "Default")
      (node (ref "J17") (pin "9") (pinfunction "9_9") (pintype "passive"))
    )
    (net (code "64") (name "/Q_23_p") (class "Default")
      (node (ref "J17") (pin "7") (pinfunction "7_7") (pintype "passive"))
    )
    (net (code "65") (name "/Q_24_n") (class "Default")
      (node (ref "J17") (pin "12") (pinfunction "12_12") (pintype "passive"))
    )
    (net (code "66") (name "/Q_24_p") (class "Default")
      (node (ref "J17") (pin "10") (pinfunction "10_10") (pintype "passive"))
    )
    (net (code "67") (name "/Q_26_n") (class "Default")
      (node (ref "J18") (pin "3") (pinfunction "3_3") (pintype "passive"))
    )
    (net (code "68") (name "/Q_26_p") (class "Default")
      (node (ref "J18") (pin "1") (pinfunction "1_1") (pintype "passive"))
    )
    (net (code "69") (name "/Q_27_n") (class "Default")
      (node (ref "J18") (pin "6") (pinfunction "6_6") (pintype "passive"))
    )
    (net (code "70") (name "/Q_27_p") (class "Default")
      (node (ref "J18") (pin "4") (pinfunction "4_4") (pintype "passive"))
    )
    (net (code "71") (name "/Q_28_n") (class "Default")
      (node (ref "J18") (pin "9") (pinfunction "9_9") (pintype "passive"))
    )
    (net (code "72") (name "/Q_28_p") (class "Default")
      (node (ref "J18") (pin "7") (pinfunction "7_7") (pintype "passive"))
    )
    (net (code "73") (name "/Q_29_n") (class "Default")
      (node (ref "J18") (pin "12") (pinfunction "12_12") (pintype "passive"))
    )
    (net (code "74") (name "/Q_29_p") (class "Default")
      (node (ref "J18") (pin "10") (pinfunction "10_10") (pintype "passive"))
    )
    (net (code "75") (name "/Q_31_n") (class "Default")
      (node (ref "J19") (pin "3") (pinfunction "3_3") (pintype "passive"))
    )
    (net (code "76") (name "/Q_31_p") (class "Default")
      (node (ref "J19") (pin "1") (pinfunction "1_1") (pintype "passive"))
    )
    (net (code "77") (name "/Q_32_n") (class "Default")
      (node (ref "J19") (pin "6") (pinfunction "6_6") (pintype "passive"))
    )
    (net (code "78") (name "/Q_32_p") (class "Default")
      (node (ref "J19") (pin "4") (pinfunction "4_4") (pintype "passive"))
    )
    (net (code "79") (name "/Q_33_n") (class "Default")
      (node (ref "J19") (pin "9") (pinfunction "9_9") (pintype "passive"))
    )
    (net (code "80") (name "/Q_33_p") (class "Default")
      (node (ref "J19") (pin "7") (pinfunction "7_7") (pintype "passive"))
    )
    (net (code "81") (name "/Q_34_n") (class "Default")
      (node (ref "J19") (pin "12") (pinfunction "12_12") (pintype "passive"))
    )
    (net (code "82") (name "/Q_34_p") (class "Default")
      (node (ref "J19") (pin "10") (pinfunction "10_10") (pintype "passive"))
    )
    (net (code "83") (name "/Q_36_n") (class "Default")
      (node (ref "J20") (pin "3") (pinfunction "3_3") (pintype "passive"))
    )
    (net (code "84") (name "/Q_36_p") (class "Default")
      (node (ref "J20") (pin "1") (pinfunction "1_1") (pintype "passive"))
    )
    (net (code "85") (name "/Q_37_n") (class "Default")
      (node (ref "J20") (pin "6") (pinfunction "6_6") (pintype "passive"))
    )
    (net (code "86") (name "/Q_37_p") (class "Default")
      (node (ref "J20") (pin "4") (pinfunction "4_4") (pintype "passive"))
    )
    (net (code "87") (name "/Q_38_n") (class "Default")
      (node (ref "J20") (pin "9") (pinfunction "9_9") (pintype "passive"))
    )
    (net (code "88") (name "/Q_38_p") (class "Default")
      (node (ref "J20") (pin "7") (pinfunction "7_7") (pintype "passive"))
    )
    (net (code "89") (name "/Q_39_n") (class "Default")
      (node (ref "J20") (pin "12") (pinfunction "12_12") (pintype "passive"))
    )
    (net (code "90") (name "/Q_39_p") (class "Default")
      (node (ref "J20") (pin "10") (pinfunction "10_10") (pintype "passive"))
    )
    (net (code "91") (name "/Q_41_n") (class "Default")
      (node (ref "J21") (pin "3") (pinfunction "3_3") (pintype "passive"))
    )
    (net (code "92") (name "/Q_41_p") (class "Default")
      (node (ref "J21") (pin "1") (pinfunction "1_1") (pintype "passive"))
    )
    (net (code "93") (name "/Q_42_n") (class "Default")
      (node (ref "J21") (pin "6") (pinfunction "6_6") (pintype "passive"))
    )
    (net (code "94") (name "/Q_42_p") (class "Default")
      (node (ref "J21") (pin "4") (pinfunction "4_4") (pintype "passive"))
    )
    (net (code "95") (name "/Q_43_n") (class "Default")
      (node (ref "J21") (pin "9") (pinfunction "9_9") (pintype "passive"))
    )
    (net (code "96") (name "/Q_43_p") (class "Default")
      (node (ref "J21") (pin "7") (pinfunction "7_7") (pintype "passive"))
    )
    (net (code "97") (name "/Q_44_n") (class "Default")
      (node (ref "J21") (pin "12") (pinfunction "12_12") (pintype "passive"))
    )
    (net (code "98") (name "/Q_44_p") (class "Default")
      (node (ref "J21") (pin "10") (pinfunction "10_10") (pintype "passive"))
    )
    (net (code "99") (name "/Q_46_n") (class "Default")
      (node (ref "J22") (pin "3") (pinfunction "3_3") (pintype "passive"))
    )
    (net (code "100") (name "/Q_46_p") (class "Default")
      (node (ref "J22") (pin "1") (pinfunction "1_1") (pintype "passive"))
    )
    (net (code "101") (name "/Q_47_n") (class "Default")
      (node (ref "J22") (pin "6") (pinfunction "6_6") (pintype "passive"))
    )
    (net (code "102") (name "/Q_47_p") (class "Default")
      (node (ref "J22") (pin "4") (pinfunction "4_4") (pintype "passive"))
    )
    (net (code "103") (name "/Q_48_n") (class "Default")
      (node (ref "J22") (pin "9") (pinfunction "9_9") (pintype "passive"))
    )
    (net (code "104") (name "/Q_48_p") (class "Default")
      (node (ref "J22") (pin "7") (pinfunction "7_7") (pintype "passive"))
    )
    (net (code "105") (name "/Q_49_n") (class "Default")
      (node (ref "J22") (pin "12") (pinfunction "12_12") (pintype "passive"))
    )
    (net (code "106") (name "/Q_49_p") (class "Default")
      (node (ref "J22") (pin "10") (pinfunction "10_10") (pintype "passive"))
    )
    (net (code "107") (name "/T_1_n") (class "Default")
      (node (ref "J4") (pin "3") (pinfunction "3_3") (pintype "passive"))
    )
    (net (code "108") (name "/T_1_p") (class "Default")
      (node (ref "J4") (pin "1") (pinfunction "1_1") (pintype "passive"))
    )
    (net (code "109") (name "/T_2_n") (class "Default")
      (node (ref "J4") (pin "6") (pinfunction "6_6") (pintype "passive"))
    )
    (net (code "110") (name "/T_2_p") (class "Default")
      (node (ref "J4") (pin "4") (pinfunction "4_4") (pintype "passive"))
    )
    (net (code "111") (name "/T_3_n") (class "Default")
      (node (ref "J4") (pin "9") (pinfunction "9_9") (pintype "passive"))
    )
    (net (code "112") (name "/T_3_p") (class "Default")
      (node (ref "J4") (pin "7") (pinfunction "7_7") (pintype "passive"))
    )
    (net (code "113") (name "/T_4_n") (class "Default")
      (node (ref "J5") (pin "3") (pinfunction "3_3") (pintype "passive"))
    )
    (net (code "114") (name "/T_4_p") (class "Default")
      (node (ref "J5") (pin "1") (pinfunction "1_1") (pintype "passive"))
    )
    (net (code "115") (name "/T_5_n") (class "Default")
      (node (ref "J5") (pin "6") (pinfunction "6_6") (pintype "passive"))
    )
    (net (code "116") (name "/T_5_p") (class "Default")
      (node (ref "J5") (pin "4") (pinfunction "4_4") (pintype "passive"))
    )
    (net (code "117") (name "/T_6_n") (class "Default")
      (node (ref "J5") (pin "9") (pinfunction "9_9") (pintype "passive"))
    )
    (net (code "118") (name "/T_6_p") (class "Default")
      (node (ref "J5") (pin "7") (pinfunction "7_7") (pintype "passive"))
    )
    (net (code "119") (name "/T_7_n") (class "Default")
      (node (ref "J6") (pin "3") (pinfunction "3_3") (pintype "passive"))
    )
    (net (code "120") (name "/T_7_p") (class "Default")
      (node (ref "J6") (pin "1") (pinfunction "1_1") (pintype "passive"))
    )
    (net (code "121") (name "/T_8_n") (class "Default")
      (node (ref "J6") (pin "6") (pinfunction "6_6") (pintype "passive"))
    )
    (net (code "122") (name "/T_8_p") (class "Default")
      (node (ref "J6") (pin "4") (pinfunction "4_4") (pintype "passive"))
    )
    (net (code "123") (name "/T_9_n") (class "Default")
      (node (ref "J6") (pin "9") (pinfunction "9_9") (pintype "passive"))
    )
    (net (code "124") (name "/T_9_p") (class "Default")
      (node (ref "J6") (pin "7") (pinfunction "7_7") (pintype "passive"))
    )
    (net (code "125") (name "/T_11_n") (class "Default")
      (node (ref "J7") (pin "3") (pinfunction "3_3") (pintype "passive"))
    )
    (net (code "126") (name "/T_11_p") (class "Default")
      (node (ref "J7") (pin "1") (pinfunction "1_1") (pintype "passive"))
    )
    (net (code "127") (name "/T_12_n") (class "Default")
      (node (ref "J7") (pin "6") (pinfunction "6_6") (pintype "passive"))
    )
    (net (code "128") (name "/T_12_p") (class "Default")
      (node (ref "J7") (pin "4") (pinfunction "4_4") (pintype "passive"))
    )
    (net (code "129") (name "/T_13_n") (class "Default")
      (node (ref "J7") (pin "9") (pinfunction "9_9") (pintype "passive"))
    )
    (net (code "130") (name "/T_13_p") (class "Default")
      (node (ref "J7") (pin "7") (pinfunction "7_7") (pintype "passive"))
    )
    (net (code "131") (name "/T_14_n") (class "Default")
      (node (ref "J8") (pin "1") (pinfunction "1_1") (pintype "passive"))
    )
    (net (code "132") (name "/T_14_p") (class "Default")
      (node (ref "J8") (pin "3") (pinfunction "3_3") (pintype "passive"))
    )
    (net (code "133") (name "/T_15_n") (class "Default")
      (node (ref "J8") (pin "6") (pinfunction "6_6") (pintype "passive"))
    )
    (net (code "134") (name "/T_15_p") (class "Default")
      (node (ref "J8") (pin "4") (pinfunction "4_4") (pintype "passive"))
    )
    (net (code "135") (name "/T_16_n") (class "Default")
      (node (ref "J8") (pin "9") (pinfunction "9_9") (pintype "passive"))
    )
    (net (code "136") (name "/T_16_p") (class "Default")
      (node (ref "J8") (pin "7") (pinfunction "7_7") (pintype "passive"))
    )
    (net (code "137") (name "/T_17_n") (class "Default")
      (node (ref "J9") (pin "3") (pinfunction "3_3") (pintype "passive"))
    )
    (net (code "138") (name "/T_17_p") (class "Default")
      (node (ref "J9") (pin "1") (pinfunction "1_1") (pintype "passive"))
    )
    (net (code "139") (name "/T_18_n") (class "Default")
      (node (ref "J9") (pin "6") (pinfunction "6_6") (pintype "passive"))
    )
    (net (code "140") (name "/T_18_p") (class "Default")
      (node (ref "J9") (pin "4") (pinfunction "4_4") (pintype "passive"))
    )
    (net (code "141") (name "/T_19_n") (class "Default")
      (node (ref "J9") (pin "9") (pinfunction "9_9") (pintype "passive"))
    )
    (net (code "142") (name "/T_19_p") (class "Default")
      (node (ref "J9") (pin "7") (pinfunction "7_7") (pintype "passive"))
    )
    (net (code "143") (name "/T_21_n") (class "Default")
      (node (ref "J10") (pin "3") (pinfunction "3_3") (pintype "passive"))
    )
    (net (code "144") (name "/T_21_p") (class "Default")
      (node (ref "J10") (pin "1") (pinfunction "1_1") (pintype "passive"))
    )
    (net (code "145") (name "/T_22_n") (class "Default")
      (node (ref "J10") (pin "6") (pinfunction "6_6") (pintype "passive"))
    )
    (net (code "146") (name "/T_22_p") (class "Default")
      (node (ref "J10") (pin "4") (pinfunction "4_4") (pintype "passive"))
    )
    (net (code "147") (name "/T_23_n") (class "Default")
      (node (ref "J10") (pin "9") (pinfunction "9_9") (pintype "passive"))
    )
    (net (code "148") (name "/T_23_p") (class "Default")
      (node (ref "J10") (pin "7") (pinfunction "7_7") (pintype "passive"))
    )
    (net (code "149") (name "/T_24_n") (class "Default")
      (node (ref "J11") (pin "3") (pinfunction "3_3") (pintype "passive"))
    )
    (net (code "150") (name "/T_24_p") (class "Default")
      (node (ref "J11") (pin "1") (pinfunction "1_1") (pintype "passive"))
    )
    (net (code "151") (name "/T_25_n") (class "Default")
      (node (ref "J11") (pin "6") (pinfunction "6_6") (pintype "passive"))
    )
    (net (code "152") (name "/T_25_p") (class "Default")
      (node (ref "J11") (pin "4") (pinfunction "4_4") (pintype "passive"))
    )
    (net (code "153") (name "/T_26_n") (class "Default")
      (node (ref "J11") (pin "9") (pinfunction "9_9") (pintype "passive"))
    )
    (net (code "154") (name "/T_26_p") (class "Default")
      (node (ref "J11") (pin "7") (pinfunction "7_7") (pintype "passive"))
    )
    (net (code "155") (name "/T_27_n") (class "Default")
      (node (ref "J12") (pin "3") (pinfunction "3_3") (pintype "passive"))
    )
    (net (code "156") (name "/T_27_p") (class "Default")
      (node (ref "J12") (pin "1") (pinfunction "1_1") (pintype "passive"))
    )
    (net (code "157") (name "/T_28_n") (class "Default")
      (node (ref "J12") (pin "6") (pinfunction "6_6") (pintype "passive"))
    )
    (net (code "158") (name "/T_28_p") (class "Default")
      (node (ref "J12") (pin "4") (pinfunction "4_4") (pintype "passive"))
    )
    (net (code "159") (name "/T_29_n") (class "Default")
      (node (ref "J12") (pin "9") (pinfunction "9_9") (pintype "passive"))
    )
    (net (code "160") (name "/T_29_p") (class "Default")
      (node (ref "J12") (pin "7") (pinfunction "7_7") (pintype "passive"))
    )
    (net (code "161") (name "GND") (class "Default")
      (node (ref "C1") (pin "1") (pinfunction "1_1") (pintype "passive"))
      (node (ref "C10") (pin "1") (pinfunction "1_1") (pintype "passive"))
      (node (ref "C11") (pin "1") (pinfunction "1_1") (pintype "passive"))
      (node (ref "C12") (pin "1") (pinfunction "1_1") (pintype "passive"))
      (node (ref "C13") (pin "1") (pinfunction "1_1") (pintype "passive"))
      (node (ref "C14") (pin "1") (pinfunction "1_1") (pintype "passive"))
      (node (ref "C15") (pin "1") (pinfunction "1_1") (pintype "passive"))
      (node (ref "C16") (pin "1") (pinfunction "1_1") (pintype "passive"))
      (node (ref "C17") (pin "1") (pinfunction "1_1") (pintype "passive"))
      (node (ref "C18") (pin "1") (pinfunction "1_1") (pintype "passive"))
      (node (ref "C19") (pin "1") (pinfunction "1_1") (pintype "passive"))
      (node (ref "C2") (pin "1") (pinfunction "1_1") (pintype "passive"))
      (node (ref "C20") (pin "1") (pinfunction "1_1") (pintype "passive"))
      (node (ref "C21") (pin "1") (pinfunction "1_1") (pintype "passive"))
      (node (ref "C22") (pin "1") (pinfunction "1_1") (pintype "passive"))
      (node (ref "C23") (pin "1") (pinfunction "1_1") (pintype "passive"))
      (node (ref "C24") (pin "1") (pinfunction "1_1") (pintype "passive"))
      (node (ref "C25") (pin "1") (pinfunction "1_1") (pintype "passive"))
      (node (ref "C26") (pin "1") (pinfunction "1_1") (pintype "passive"))
      (node (ref "C27") (pin "1") (pinfunction "1_1") (pintype "passive"))
      (node (ref "C28") (pin "1") (pinfunction "1_1") (pintype "passive"))
      (node (ref "C29") (pin "1") (pinfunction "1_1") (pintype "passive"))
      (node (ref "C3") (pin "1") (pinfunction "1_1") (pintype "passive"))
      (node (ref "C30") (pin "1") (pinfunction "1_1") (pintype "passive"))
      (node (ref "C31") (pin "1") (pinfunction "1_1") (pintype "passive"))
      (node (ref "C32") (pin "1") (pinfunction "1_1") (pintype "passive"))
      (node (ref "C33") (pin "1") (pinfunction "1_1") (pintype "passive"))
      (node (ref "C34") (pin "1") (pinfunction "1_1") (pintype "passive"))
      (node (ref "C35") (pin "1") (pinfunction "1_1") (pintype "passive"))
      (node (ref "C36") (pin "1") (pinfunction "1_1") (pintype "passive"))
      (node (ref "C37") (pin "1") (pinfunction "1_1") (pintype "passive"))
      (node (ref "C38") (pin "1") (pinfunction "1_1") (pintype "passive"))
      (node (ref "C39") (pin "1") (pinfunction "1_1") (pintype "passive"))
      (node (ref "C4") (pin "1") (pinfunction "1_1") (pintype "passive"))
      (node (ref "C40") (pin "1") (pinfunction "1_1") (pintype "passive"))
      (node (ref "C41") (pin "1") (pinfunction "1_1") (pintype "passive"))
      (node (ref "C42") (pin "1") (pinfunction "1_1") (pintype "passive"))
      (node (ref "C43") (pin "1") (pinfunction "1_1") (pintype "passive"))
      (node (ref "C44") (pin "1") (pinfunction "1_1") (pintype "passive"))
      (node (ref "C45") (pin "1") (pinfunction "1_1") (pintype "passive"))
      (node (ref "C46") (pin "1") (pinfunction "1_1") (pintype "passive"))
      (node (ref "C47") (pin "1") (pinfunction "1_1") (pintype "passive"))
      (node (ref "C48") (pin "1") (pinfunction "1_1") (pintype "passive"))
      (node (ref "C49") (pin "1") (pinfunction "1_1") (pintype "passive"))
      (node (ref "C5") (pin "1") (pinfunction "1_1") (pintype "passive"))
      (node (ref "C50") (pin "1") (pinfunction "1_1") (pintype "passive"))
      (node (ref "C51") (pin "1") (pinfunction "1_1") (pintype "passive"))
      (node (ref "C52") (pin "1") (pinfunction "1_1") (pintype "passive"))
      (node (ref "C53") (pin "1") (pinfunction "1_1") (pintype "passive"))
      (node (ref "C54") (pin "1") (pinfunction "1_1") (pintype "passive"))
      (node (ref "C55") (pin "1") (pinfunction "1_1") (pintype "passive"))
      (node (ref "C56") (pin "1") (pinfunction "1_1") (pintype "passive"))
      (node (ref "C57") (pin "1") (pinfunction "1_1") (pintype "passive"))
      (node (ref "C58") (pin "1") (pinfunction "1_1") (pintype "passive"))
      (node (ref "C59") (pin "1") (pinfunction "1_1") (pintype "passive"))
      (node (ref "C6") (pin "1") (pinfunction "1_1") (pintype "passive"))
      (node (ref "C60") (pin "1") (pinfunction "1_1") (pintype "passive"))
      (node (ref "C61") (pin "1") (pinfunction "1_1") (pintype "passive"))
      (node (ref "C62") (pin "1") (pinfunction "1_1") (pintype "passive"))
      (node (ref "C63") (pin "1") (pinfunction "1_1") (pintype "passive"))
      (node (ref "C64") (pin "1") (pinfunction "1_1") (pintype "passive"))
      (node (ref "C65") (pin "1") (pinfunction "1_1") (pintype "passive"))
      (node (ref "C66") (pin "1") (pinfunction "1_1") (pintype "passive"))
      (node (ref "C67") (pin "1") (pinfunction "1_1") (pintype "passive"))
      (node (ref "C68") (pin "1") (pinfunction "1_1") (pintype "passive"))
      (node (ref "C69") (pin "1") (pinfunction "1_1") (pintype "passive"))
      (node (ref "C7") (pin "1") (pinfunction "1_1") (pintype "passive"))
      (node (ref "C70") (pin "1") (pinfunction "1_1") (pintype "passive"))
      (node (ref "C71") (pin "1") (pinfunction "1_1") (pintype "passive"))
      (node (ref "C72") (pin "1") (pinfunction "1_1") (pintype "passive"))
      (node (ref "C73") (pin "1") (pinfunction "1_1") (pintype "passive"))
      (node (ref "C74") (pin "1") (pinfunction "1_1") (pintype "passive"))
      (node (ref "C75") (pin "1") (pinfunction "1_1") (pintype "passive"))
      (node (ref "C76") (pin "1") (pinfunction "1_1") (pintype "passive"))
      (node (ref "C77") (pin "1") (pinfunction "1_1") (pintype "passive"))
      (node (ref "C78") (pin "1") (pinfunction "1_1") (pintype "passive"))
      (node (ref "C79") (pin "1") (pinfunction "1_1") (pintype "passive"))
      (node (ref "C8") (pin "1") (pinfunction "1_1") (pintype "passive"))
      (node (ref "C80") (pin "1") (pinfunction "1_1") (pintype "passive"))
      (node (ref "C81") (pin "1") (pinfunction "1_1") (pintype "passive"))
      (node (ref "C82") (pin "1") (pinfunction "1_1") (pintype "passive"))
      (node (ref "C83") (pin "1") (pinfunction "1_1") (pintype "passive"))
      (node (ref "C84") (pin "1") (pinfunction "1_1") (pintype "passive"))
      (node (ref "C85") (pin "1") (pinfunction "1_1") (pintype "passive"))
      (node (ref "C86") (pin "1") (pinfunction "1_1") (pintype "passive"))
      (node (ref "C87") (pin "1") (pinfunction "1_1") (pintype "passive"))
      (node (ref "C88") (pin "1") (pinfunction "1_1") (pintype "passive"))
      (node (ref "C89") (pin "1") (pinfunction "1_1") (pintype "passive"))
      (node (ref "C9") (pin "1") (pinfunction "1_1") (pintype "passive"))
    )
    (net (code "162") (name "Net-(C1-Pad2)") (class "Default")
      (node (ref "C1") (pin "2") (pinfunction "2_2") (pintype "passive"))
      (node (ref "J5") (pin "2") (pinfunction "2_2") (pintype "passive"))
    )
    (net (code "163") (name "Net-(C2-Pad2)") (class "Default")
      (node (ref "C2") (pin "2") (pinfunction "2_2") (pintype "passive"))
      (node (ref "J4") (pin "2") (pinfunction "2_2") (pintype "passive"))
    )
    (net (code "164") (name "Net-(C3-Pad2)") (class "Default")
      (node (ref "C3") (pin "2") (pinfunction "2_2") (pintype "passive"))
      (node (ref "J4") (pin "5") (pinfunction "5_5") (pintype "passive"))
    )
    (net (code "165") (name "Net-(C4-Pad2)") (class "Default")
      (node (ref "C4") (pin "2") (pinfunction "2_2") (pintype "passive"))
      (node (ref "J5") (pin "5") (pinfunction "5_5") (pintype "passive"))
    )
    (net (code "166") (name "Net-(C5-Pad2)") (class "Default")
      (node (ref "C5") (pin "2") (pinfunction "2_2") (pintype "passive"))
      (node (ref "J4") (pin "8") (pinfunction "8_8") (pintype "passive"))
    )
    (net (code "167") (name "Net-(C6-Pad2)") (class "Default")
      (node (ref "C6") (pin "2") (pinfunction "2_2") (pintype "passive"))
      (node (ref "J5") (pin "8") (pinfunction "8_8") (pintype "passive"))
    )
    (net (code "168") (name "Net-(C7-Pad2)") (class "Default")
      (node (ref "C7") (pin "2") (pinfunction "2_2") (pintype "passive"))
      (node (ref "J4") (pin "11") (pinfunction "11_11") (pintype "passive"))
    )
    (net (code "169") (name "Net-(C8-Pad2)") (class "Default")
      (node (ref "C8") (pin "2") (pinfunction "2_2") (pintype "passive"))
      (node (ref "J5") (pin "11") (pinfunction "11_11") (pintype "passive"))
    )
    (net (code "170") (name "Net-(C9-Pad2)") (class "Default")
      (node (ref "C9") (pin "2") (pinfunction "2_2") (pintype "passive"))
      (node (ref "J6") (pin "2") (pinfunction "2_2") (pintype "passive"))
    )
    (net (code "171") (name "Net-(C10-Pad2)") (class "Default")
      (node (ref "C10") (pin "2") (pinfunction "2_2") (pintype "passive"))
      (node (ref "J7") (pin "2") (pinfunction "2_2") (pintype "passive"))
    )
    (net (code "172") (name "Net-(C11-Pad2)") (class "Default")
      (node (ref "C11") (pin "2") (pinfunction "2_2") (pintype "passive"))
      (node (ref "J8") (pin "2") (pinfunction "2_2") (pintype "passive"))
    )
    (net (code "173") (name "Net-(C12-Pad2)") (class "Default")
      (node (ref "C12") (pin "2") (pinfunction "2_2") (pintype "passive"))
      (node (ref "J9") (pin "2") (pinfunction "2_2") (pintype "passive"))
    )
    (net (code "174") (name "Net-(C13-Pad2)") (class "Default")
      (node (ref "C13") (pin "2") (pinfunction "2_2") (pintype "passive"))
      (node (ref "J6") (pin "5") (pinfunction "5_5") (pintype "passive"))
    )
    (net (code "175") (name "Net-(C14-Pad2)") (class "Default")
      (node (ref "C14") (pin "2") (pinfunction "2_2") (pintype "passive"))
      (node (ref "J7") (pin "5") (pinfunction "5_5") (pintype "passive"))
    )
    (net (code "176") (name "Net-(C15-Pad2)") (class "Default")
      (node (ref "C15") (pin "2") (pinfunction "2_2") (pintype "passive"))
      (node (ref "J8") (pin "5") (pinfunction "5_5") (pintype "passive"))
    )
    (net (code "177") (name "Net-(C16-Pad2)") (class "Default")
      (node (ref "C16") (pin "2") (pinfunction "2_2") (pintype "passive"))
      (node (ref "J9") (pin "5") (pinfunction "5_5") (pintype "passive"))
    )
    (net (code "178") (name "Net-(C17-Pad2)") (class "Default")
      (node (ref "C17") (pin "2") (pinfunction "2_2") (pintype "passive"))
      (node (ref "J6") (pin "8") (pinfunction "8_8") (pintype "passive"))
    )
    (net (code "179") (name "Net-(C18-Pad2)") (class "Default")
      (node (ref "C18") (pin "2") (pinfunction "2_2") (pintype "passive"))
      (node (ref "J7") (pin "8") (pinfunction "8_8") (pintype "passive"))
    )
    (net (code "180") (name "Net-(C19-Pad2)") (class "Default")
      (node (ref "C19") (pin "2") (pinfunction "2_2") (pintype "passive"))
      (node (ref "J8") (pin "8") (pinfunction "8_8") (pintype "passive"))
    )
    (net (code "181") (name "Net-(C20-Pad2)") (class "Default")
      (node (ref "C20") (pin "2") (pinfunction "2_2") (pintype "passive"))
      (node (ref "J9") (pin "8") (pinfunction "8_8") (pintype "passive"))
    )
    (net (code "182") (name "Net-(C21-Pad2)") (class "Default")
      (node (ref "C21") (pin "2") (pinfunction "2_2") (pintype "passive"))
      (node (ref "J6") (pin "11") (pinfunction "11_11") (pintype "passive"))
    )
    (net (code "183") (name "Net-(C22-Pad2)") (class "Default")
      (node (ref "C22") (pin "2") (pinfunction "2_2") (pintype "passive"))
      (node (ref "J7") (pin "11") (pinfunction "11_11") (pintype "passive"))
    )
    (net (code "184") (name "Net-(C23-Pad2)") (class "Default")
      (node (ref "C23") (pin "2") (pinfunction "2_2") (pintype "passive"))
      (node (ref "J8") (pin "11") (pinfunction "11_11") (pintype "passive"))
    )
    (net (code "185") (name "Net-(C24-Pad2)") (class "Default")
      (node (ref "C24") (pin "2") (pinfunction "2_2") (pintype "passive"))
      (node (ref "J9") (pin "11") (pinfunction "11_11") (pintype "passive"))
    )
    (net (code "186") (name "Net-(C25-Pad2)") (class "Default")
      (node (ref "C25") (pin "2") (pinfunction "2_2") (pintype "passive"))
      (node (ref "J6") (pin "16") (pinfunction "16_16") (pintype "passive"))
    )
    (net (code "187") (name "Net-(C26-Pad2)") (class "Default")
      (node (ref "C26") (pin "2") (pinfunction "2_2") (pintype "passive"))
      (node (ref "J9") (pin "16") (pinfunction "16_16") (pintype "passive"))
    )
    (net (code "188") (name "Net-(C27-Pad2)") (class "Default")
      (node (ref "C27") (pin "2") (pinfunction "2_2") (pintype "passive"))
      (node (ref "J10") (pin "2") (pinfunction "2_2") (pintype "passive"))
    )
    (net (code "189") (name "Net-(C28-Pad2)") (class "Default")
      (node (ref "C28") (pin "2") (pinfunction "2_2") (pintype "passive"))
      (node (ref "J11") (pin "2") (pinfunction "2_2") (pintype "passive"))
    )
    (net (code "190") (name "Net-(C29-Pad2)") (class "Default")
      (node (ref "C29") (pin "2") (pinfunction "2_2") (pintype "passive"))
      (node (ref "J12") (pin "2") (pinfunction "2_2") (pintype "passive"))
    )
    (net (code "191") (name "Net-(C30-Pad2)") (class "Default")
      (node (ref "C30") (pin "2") (pinfunction "2_2") (pintype "passive"))
      (node (ref "J13") (pin "2") (pinfunction "2_2") (pintype "passive"))
    )
    (net (code "192") (name "Net-(C31-Pad2)") (class "Default")
      (node (ref "C31") (pin "2") (pinfunction "2_2") (pintype "passive"))
      (node (ref "J14") (pin "2") (pinfunction "2_2") (pintype "passive"))
    )
    (net (code "193") (name "Net-(C32-Pad2)") (class "Default")
      (node (ref "C32") (pin "2") (pinfunction "2_2") (pintype "passive"))
      (node (ref "J15") (pin "2") (pinfunction "2_2") (pintype "passive"))
    )
    (net (code "194") (name "Net-(C33-Pad2)") (class "Default")
      (node (ref "C33") (pin "2") (pinfunction "2_2") (pintype "passive"))
      (node (ref "J10") (pin "5") (pinfunction "5_5") (pintype "passive"))
    )
    (net (code "195") (name "Net-(C34-Pad2)") (class "Default")
      (node (ref "C34") (pin "2") (pinfunction "2_2") (pintype "passive"))
      (node (ref "J11") (pin "5") (pinfunction "5_5") (pintype "passive"))
    )
    (net (code "196") (name "Net-(C35-Pad2)") (class "Default")
      (node (ref "C35") (pin "2") (pinfunction "2_2") (pintype "passive"))
      (node (ref "J12") (pin "5") (pinfunction "5_5") (pintype "passive"))
    )
    (net (code "197") (name "Net-(C36-Pad2)") (class "Default")
      (node (ref "C36") (pin "2") (pinfunction "2_2") (pintype "passive"))
      (node (ref "J13") (pin "5") (pinfunction "5_5") (pintype "passive"))
    )
    (net (code "198") (name "Net-(C37-Pad2)") (class "Default")
      (node (ref "C37") (pin "2") (pinfunction "2_2") (pintype "passive"))
      (node (ref "J14") (pin "5") (pinfunction "5_5") (pintype "passive"))
    )
    (net (code "199") (name "Net-(C38-Pad2)") (class "Default")
      (node (ref "C38") (pin "2") (pinfunction "2_2") (pintype "passive"))
      (node (ref "J15") (pin "5") (pinfunction "5_5") (pintype "passive"))
    )
    (net (code "200") (name "Net-(C39-Pad2)") (class "Default")
      (node (ref "C39") (pin "2") (pinfunction "2_2") (pintype "passive"))
      (node (ref "J10") (pin "8") (pinfunction "8_8") (pintype "passive"))
    )
    (net (code "201") (name "Net-(C40-Pad2)") (class "Default")
      (node (ref "C40") (pin "2") (pinfunction "2_2") (pintype "passive"))
      (node (ref "J11") (pin "8") (pinfunction "8_8") (pintype "passive"))
    )
    (net (code "202") (name "Net-(C41-Pad2)") (class "Default")
      (node (ref "C41") (pin "2") (pinfunction "2_2") (pintype "passive"))
      (node (ref "J12") (pin "8") (pinfunction "8_8") (pintype "passive"))
    )
    (net (code "203") (name "Net-(C42-Pad2)") (class "Default")
      (node (ref "C42") (pin "2") (pinfunction "2_2") (pintype "passive"))
      (node (ref "J13") (pin "8") (pinfunction "8_8") (pintype "passive"))
    )
    (net (code "204") (name "Net-(C43-Pad2)") (class "Default")
      (node (ref "C43") (pin "2") (pinfunction "2_2") (pintype "passive"))
      (node (ref "J14") (pin "8") (pinfunction "8_8") (pintype "passive"))
    )
    (net (code "205") (name "Net-(C44-Pad2)") (class "Default")
      (node (ref "C44") (pin "2") (pinfunction "2_2") (pintype "passive"))
      (node (ref "J15") (pin "8") (pinfunction "8_8") (pintype "passive"))
    )
    (net (code "206") (name "Net-(C45-Pad2)") (class "Default")
      (node (ref "C45") (pin "2") (pinfunction "2_2") (pintype "passive"))
      (node (ref "J10") (pin "11") (pinfunction "11_11") (pintype "passive"))
    )
    (net (code "207") (name "Net-(C46-Pad2)") (class "Default")
      (node (ref "C46") (pin "2") (pinfunction "2_2") (pintype "passive"))
      (node (ref "J11") (pin "11") (pinfunction "11_11") (pintype "passive"))
    )
    (net (code "208") (name "Net-(C47-Pad2)") (class "Default")
      (node (ref "C47") (pin "2") (pinfunction "2_2") (pintype "passive"))
      (node (ref "J12") (pin "11") (pinfunction "11_11") (pintype "passive"))
    )
    (net (code "209") (name "Net-(C48-Pad2)") (class "Default")
      (node (ref "C48") (pin "2") (pinfunction "2_2") (pintype "passive"))
      (node (ref "J13") (pin "11") (pinfunction "11_11") (pintype "passive"))
    )
    (net (code "210") (name "Net-(C49-Pad2)") (class "Default")
      (node (ref "C49") (pin "2") (pinfunction "2_2") (pintype "passive"))
      (node (ref "J14") (pin "11") (pinfunction "11_11") (pintype "passive"))
    )
    (net (code "211") (name "Net-(C50-Pad2)") (class "Default")
      (node (ref "C50") (pin "2") (pinfunction "2_2") (pintype "passive"))
      (node (ref "J15") (pin "11") (pinfunction "11_11") (pintype "passive"))
    )
    (net (code "212") (name "Net-(C51-Pad2)") (class "Default")
      (node (ref "C51") (pin "2") (pinfunction "2_2") (pintype "passive"))
      (node (ref "J12") (pin "16") (pinfunction "16_16") (pintype "passive"))
    )
    (net (code "213") (name "Net-(C52-Pad2)") (class "Default")
      (node (ref "C52") (pin "2") (pinfunction "2_2") (pintype "passive"))
      (node (ref "J13") (pin "16") (pinfunction "16_16") (pintype "passive"))
    )
    (net (code "214") (name "Net-(C53-Pad2)") (class "Default")
      (node (ref "C53") (pin "2") (pinfunction "2_2") (pintype "passive"))
      (node (ref "J14") (pin "16") (pinfunction "16_16") (pintype "passive"))
    )
    (net (code "215") (name "Net-(C54-Pad2)") (class "Default")
      (node (ref "C54") (pin "2") (pinfunction "2_2") (pintype "passive"))
      (node (ref "J15") (pin "16") (pinfunction "16_16") (pintype "passive"))
    )
    (net (code "216") (name "Net-(C55-Pad2)") (class "Default")
      (node (ref "C55") (pin "2") (pinfunction "2_2") (pintype "passive"))
      (node (ref "J16") (pin "2") (pinfunction "2_2") (pintype "passive"))
    )
    (net (code "217") (name "Net-(C56-Pad2)") (class "Default")
      (node (ref "C56") (pin "2") (pinfunction "2_2") (pintype "passive"))
      (node (ref "J17") (pin "2") (pinfunction "2_2") (pintype "passive"))
    )
    (net (code "218") (name "Net-(C57-Pad2)") (class "Default")
      (node (ref "C57") (pin "2") (pinfunction "2_2") (pintype "passive"))
      (node (ref "J18") (pin "2") (pinfunction "2_2") (pintype "passive"))
    )
    (net (code "219") (name "Net-(C58-Pad2)") (class "Default")
      (node (ref "C58") (pin "2") (pinfunction "2_2") (pintype "passive"))
      (node (ref "J19") (pin "2") (pinfunction "2_2") (pintype "passive"))
    )
    (net (code "220") (name "Net-(C59-Pad2)") (class "Default")
      (node (ref "C59") (pin "2") (pinfunction "2_2") (pintype "passive"))
      (node (ref "J20") (pin "2") (pinfunction "2_2") (pintype "passive"))
    )
    (net (code "221") (name "Net-(C60-Pad2)") (class "Default")
      (node (ref "C60") (pin "2") (pinfunction "2_2") (pintype "passive"))
      (node (ref "J16") (pin "5") (pinfunction "5_5") (pintype "passive"))
    )
    (net (code "222") (name "Net-(C61-Pad2)") (class "Default")
      (node (ref "C61") (pin "2") (pinfunction "2_2") (pintype "passive"))
      (node (ref "J17") (pin "5") (pinfunction "5_5") (pintype "passive"))
    )
    (net (code "223") (name "Net-(C62-Pad2)") (class "Default")
      (node (ref "C62") (pin "2") (pinfunction "2_2") (pintype "passive"))
      (node (ref "J18") (pin "5") (pinfunction "5_5") (pintype "passive"))
    )
    (net (code "224") (name "Net-(C63-Pad2)") (class "Default")
      (node (ref "C63") (pin "2") (pinfunction "2_2") (pintype "passive"))
      (node (ref "J19") (pin "5") (pinfunction "5_5") (pintype "passive"))
    )
    (net (code "225") (name "Net-(C64-Pad2)") (class "Default")
      (node (ref "C64") (pin "2") (pinfunction "2_2") (pintype "passive"))
      (node (ref "J20") (pin "5") (pinfunction "5_5") (pintype "passive"))
    )
    (net (code "226") (name "Net-(C65-Pad2)") (class "Default")
      (node (ref "C65") (pin "2") (pinfunction "2_2") (pintype "passive"))
      (node (ref "J16") (pin "8") (pinfunction "8_8") (pintype "passive"))
    )
    (net (code "227") (name "Net-(C66-Pad2)") (class "Default")
      (node (ref "C66") (pin "2") (pinfunction "2_2") (pintype "passive"))
      (node (ref "J17") (pin "8") (pinfunction "8_8") (pintype "passive"))
    )
    (net (code "228") (name "Net-(C67-Pad2)") (class "Default")
      (node (ref "C67") (pin "2") (pinfunction "2_2") (pintype "passive"))
      (node (ref "J18") (pin "8") (pinfunction "8_8") (pintype "passive"))
    )
    (net (code "229") (name "Net-(C68-Pad2)") (class "Default")
      (node (ref "C68") (pin "2") (pinfunction "2_2") (pintype "passive"))
      (node (ref "J19") (pin "8") (pinfunction "8_8") (pintype "passive"))
    )
    (net (code "230") (name "Net-(C69-Pad2)") (class "Default")
      (node (ref "C69") (pin "2") (pinfunction "2_2") (pintype "passive"))
      (node (ref "J20") (pin "8") (pinfunction "8_8") (pintype "passive"))
    )
    (net (code "231") (name "Net-(C70-Pad2)") (class "Default")
      (node (ref "C70") (pin "2") (pinfunction "2_2") (pintype "passive"))
      (node (ref "J16") (pin "11") (pinfunction "11_11") (pintype "passive"))
    )
    (net (code "232") (name "Net-(C71-Pad2)") (class "Default")
      (node (ref "C71") (pin "2") (pinfunction "2_2") (pintype "passive"))
      (node (ref "J17") (pin "11") (pinfunction "11_11") (pintype "passive"))
    )
    (net (code "233") (name "Net-(C72-Pad2)") (class "Default")
      (node (ref "C72") (pin "2") (pinfunction "2_2") (pintype "passive"))
      (node (ref "J18") (pin "11") (pinfunction "11_11") (pintype "passive"))
    )
    (net (code "234") (name "Net-(C73-Pad2)") (class "Default")
      (node (ref "C73") (pin "2") (pinfunction "2_2") (pintype "passive"))
      (node (ref "J19") (pin "11") (pinfunction "11_11") (pintype "passive"))
    )
    (net (code "235") (name "Net-(C74-Pad2)") (class "Default")
      (node (ref "C74") (pin "2") (pinfunction "2_2") (pintype "passive"))
      (node (ref "J20") (pin "11") (pinfunction "11_11") (pintype "passive"))
    )
    (net (code "236") (name "Net-(C75-Pad2)") (class "Default")
      (node (ref "C75") (pin "2") (pinfunction "2_2") (pintype "passive"))
      (node (ref "J16") (pin "16") (pinfunction "16_16") (pintype "passive"))
    )
    (net (code "237") (name "Net-(C76-Pad2)") (class "Default")
      (node (ref "C76") (pin "2") (pinfunction "2_2") (pintype "passive"))
      (node (ref "J17") (pin "16") (pinfunction "16_16") (pintype "passive"))
    )
    (net (code "238") (name "Net-(C77-Pad2)") (class "Default")
      (node (ref "C77") (pin "2") (pinfunction "2_2") (pintype "passive"))
      (node (ref "J18") (pin "16") (pinfunction "16_16") (pintype "passive"))
    )
    (net (code "239") (name "Net-(C78-Pad2)") (class "Default")
      (node (ref "C78") (pin "2") (pinfunction "2_2") (pintype "passive"))
      (node (ref "J19") (pin "16") (pinfunction "16_16") (pintype "passive"))
    )
    (net (code "240") (name "Net-(C79-Pad2)") (class "Default")
      (node (ref "C79") (pin "2") (pinfunction "2_2") (pintype "passive"))
      (node (ref "J20") (pin "16") (pinfunction "16_16") (pintype "passive"))
    )
    (net (code "241") (name "Net-(C80-Pad2)") (class "Default")
      (node (ref "C80") (pin "2") (pinfunction "2_2") (pintype "passive"))
      (node (ref "J21") (pin "2") (pinfunction "2_2") (pintype "passive"))
    )
    (net (code "242") (name "Net-(C81-Pad2)") (class "Default")
      (node (ref "C81") (pin "2") (pinfunction "2_2") (pintype "passive"))
      (node (ref "J22") (pin "2") (pinfunction "2_2") (pintype "passive"))
    )
    (net (code "243") (name "Net-(C82-Pad2)") (class "Default")
      (node (ref "C82") (pin "2") (pinfunction "2_2") (pintype "passive"))
      (node (ref "J21") (pin "5") (pinfunction "5_5") (pintype "passive"))
    )
    (net (code "244") (name "Net-(C83-Pad2)") (class "Default")
      (node (ref "C83") (pin "2") (pinfunction "2_2") (pintype "passive"))
      (node (ref "J22") (pin "5") (pinfunction "5_5") (pintype "passive"))
    )
    (net (code "245") (name "Net-(C84-Pad2)") (class "Default")
      (node (ref "C84") (pin "2") (pinfunction "2_2") (pintype "passive"))
      (node (ref "J21") (pin "8") (pinfunction "8_8") (pintype "passive"))
    )
    (net (code "246") (name "Net-(C85-Pad2)") (class "Default")
      (node (ref "C85") (pin "2") (pinfunction "2_2") (pintype "passive"))
      (node (ref "J22") (pin "8") (pinfunction "8_8") (pintype "passive"))
    )
    (net (code "247") (name "Net-(C86-Pad2)") (class "Default")
      (node (ref "C86") (pin "2") (pinfunction "2_2") (pintype "passive"))
      (node (ref "J21") (pin "11") (pinfunction "11_11") (pintype "passive"))
    )
    (net (code "248") (name "Net-(C87-Pad2)") (class "Default")
      (node (ref "C87") (pin "2") (pinfunction "2_2") (pintype "passive"))
      (node (ref "J22") (pin "11") (pinfunction "11_11") (pintype "passive"))
    )
    (net (code "249") (name "Net-(C88-Pad2)") (class "Default")
      (node (ref "C88") (pin "2") (pinfunction "2_2") (pintype "passive"))
      (node (ref "J21") (pin "16") (pinfunction "16_16") (pintype "passive"))
    )
    (net (code "250") (name "Net-(C89-Pad2)") (class "Default")
      (node (ref "C89") (pin "2") (pinfunction "2_2") (pintype "passive"))
      (node (ref "J22") (pin "16") (pinfunction "16_16") (pintype "passive"))
    )
    (net (code "251") (name "unconnected-(J4-Pad10)") (class "Default")
      (node (ref "J4") (pin "10") (pinfunction "10_10") (pintype "passive"))
    )
    (net (code "252") (name "unconnected-(J4-Pad12)") (class "Default")
      (node (ref "J4") (pin "12") (pinfunction "12_12") (pintype "passive"))
    )
    (net (code "253") (name "unconnected-(J4-Pad13)") (class "Default")
      (node (ref "J4") (pin "13") (pinfunction "13_13") (pintype "passive"))
    )
    (net (code "254") (name "unconnected-(J4-Pad14)") (class "Default")
      (node (ref "J4") (pin "14") (pinfunction "14_14") (pintype "passive"))
    )
    (net (code "255") (name "unconnected-(J4-Pad15)") (class "Default")
      (node (ref "J4") (pin "15") (pinfunction "15_15") (pintype "passive"))
    )
    (net (code "256") (name "unconnected-(J4-Pad16)") (class "Default")
      (node (ref "J4") (pin "16") (pinfunction "16_16") (pintype "passive"))
    )
    (net (code "257") (name "unconnected-(J4-Pad17)") (class "Default")
      (node (ref "J4") (pin "17") (pinfunction "17_17") (pintype "passive"))
    )
    (net (code "258") (name "unconnected-(J4-Pad18)") (class "Default")
      (node (ref "J4") (pin "18") (pinfunction "18_18") (pintype "passive"))
    )
    (net (code "259") (name "unconnected-(J4-Pad19)") (class "Default")
      (node (ref "J4") (pin "19") (pinfunction "19_19") (pintype "passive"))
    )
    (net (code "260") (name "unconnected-(J4-Pad20)") (class "Default")
      (node (ref "J4") (pin "20") (pinfunction "20_20") (pintype "passive"))
    )
    (net (code "261") (name "unconnected-(J4-Pad21)") (class "Default")
      (node (ref "J4") (pin "21") (pinfunction "21_21") (pintype "passive"))
    )
    (net (code "262") (name "unconnected-(J4-Pad22)") (class "Default")
      (node (ref "J4") (pin "22") (pinfunction "22_22") (pintype "passive"))
    )
    (net (code "263") (name "unconnected-(J4-Pad23)") (class "Default")
      (node (ref "J4") (pin "23") (pinfunction "23_23") (pintype "passive"))
    )
    (net (code "264") (name "unconnected-(J4-Pad24)") (class "Default")
      (node (ref "J4") (pin "24") (pinfunction "24_24") (pintype "passive"))
    )
    (net (code "265") (name "unconnected-(J5-Pad10)") (class "Default")
      (node (ref "J5") (pin "10") (pinfunction "10_10") (pintype "passive"))
    )
    (net (code "266") (name "unconnected-(J5-Pad12)") (class "Default")
      (node (ref "J5") (pin "12") (pinfunction "12_12") (pintype "passive"))
    )
    (net (code "267") (name "unconnected-(J5-Pad13)") (class "Default")
      (node (ref "J5") (pin "13") (pinfunction "13_13") (pintype "passive"))
    )
    (net (code "268") (name "unconnected-(J5-Pad14)") (class "Default")
      (node (ref "J5") (pin "14") (pinfunction "14_14") (pintype "passive"))
    )
    (net (code "269") (name "unconnected-(J5-Pad15)") (class "Default")
      (node (ref "J5") (pin "15") (pinfunction "15_15") (pintype "passive"))
    )
    (net (code "270") (name "unconnected-(J5-Pad16)") (class "Default")
      (node (ref "J5") (pin "16") (pinfunction "16_16") (pintype "passive"))
    )
    (net (code "271") (name "unconnected-(J5-Pad17)") (class "Default")
      (node (ref "J5") (pin "17") (pinfunction "17_17") (pintype "passive"))
    )
    (net (code "272") (name "unconnected-(J5-Pad18)") (class "Default")
      (node (ref "J5") (pin "18") (pinfunction "18_18") (pintype "passive"))
    )
    (net (code "273") (name "unconnected-(J5-Pad19)") (class "Default")
      (node (ref "J5") (pin "19") (pinfunction "19_19") (pintype "passive"))
    )
    (net (code "274") (name "unconnected-(J5-Pad20)") (class "Default")
      (node (ref "J5") (pin "20") (pinfunction "20_20") (pintype "passive"))
    )
    (net (code "275") (name "unconnected-(J5-Pad21)") (class "Default")
      (node (ref "J5") (pin "21") (pinfunction "21_21") (pintype "passive"))
    )
    (net (code "276") (name "unconnected-(J5-Pad22)") (class "Default")
      (node (ref "J5") (pin "22") (pinfunction "22_22") (pintype "passive"))
    )
    (net (code "277") (name "unconnected-(J5-Pad23)") (class "Default")
      (node (ref "J5") (pin "23") (pinfunction "23_23") (pintype "passive"))
    )
    (net (code "278") (name "unconnected-(J5-Pad24)") (class "Default")
      (node (ref "J5") (pin "24") (pinfunction "24_24") (pintype "passive"))
    )
    (net (code "279") (name "unconnected-(J6-Pad10)") (class "Default")
      (node (ref "J6") (pin "10") (pinfunction "10_10") (pintype "passive"))
    )
    (net (code "280") (name "unconnected-(J6-Pad12)") (class "Default")
      (node (ref "J6") (pin "12") (pinfunction "12_12") (pintype "passive"))
    )
    (net (code "281") (name "unconnected-(J6-Pad13)") (class "Default")
      (node (ref "J6") (pin "13") (pinfunction "13_13") (pintype "passive"))
    )
    (net (code "282") (name "unconnected-(J6-Pad14)") (class "Default")
      (node (ref "J6") (pin "14") (pinfunction "14_14") (pintype "passive"))
    )
    (net (code "283") (name "unconnected-(J6-Pad18)") (class "Default")
      (node (ref "J6") (pin "18") (pinfunction "18_18") (pintype "passive"))
    )
    (net (code "284") (name "unconnected-(J6-Pad19)") (class "Default")
      (node (ref "J6") (pin "19") (pinfunction "19_19") (pintype "passive"))
    )
    (net (code "285") (name "unconnected-(J6-Pad20)") (class "Default")
      (node (ref "J6") (pin "20") (pinfunction "20_20") (pintype "passive"))
    )
    (net (code "286") (name "unconnected-(J6-Pad21)") (class "Default")
      (node (ref "J6") (pin "21") (pinfunction "21_21") (pintype "passive"))
    )
    (net (code "287") (name "unconnected-(J6-Pad22)") (class "Default")
      (node (ref "J6") (pin "22") (pinfunction "22_22") (pintype "passive"))
    )
    (net (code "288") (name "unconnected-(J6-Pad23)") (class "Default")
      (node (ref "J6") (pin "23") (pinfunction "23_23") (pintype "passive"))
    )
    (net (code "289") (name "unconnected-(J6-Pad24)") (class "Default")
      (node (ref "J6") (pin "24") (pinfunction "24_24") (pintype "passive"))
    )
    (net (code "290") (name "unconnected-(J7-Pad10)") (class "Default")
      (node (ref "J7") (pin "10") (pinfunction "10_10") (pintype "passive"))
    )
    (net (code "291") (name "unconnected-(J7-Pad12)") (class "Default")
      (node (ref "J7") (pin "12") (pinfunction "12_12") (pintype "passive"))
    )
    (net (code "292") (name "unconnected-(J7-Pad13)") (class "Default")
      (node (ref "J7") (pin "13") (pinfunction "13_13") (pintype "passive"))
    )
    (net (code "293") (name "unconnected-(J7-Pad14)") (class "Default")
      (node (ref "J7") (pin "14") (pinfunction "14_14") (pintype "passive"))
    )
    (net (code "294") (name "unconnected-(J7-Pad15)") (class "Default")
      (node (ref "J7") (pin "15") (pinfunction "15_15") (pintype "passive"))
    )
    (net (code "295") (name "unconnected-(J7-Pad16)") (class "Default")
      (node (ref "J7") (pin "16") (pinfunction "16_16") (pintype "passive"))
    )
    (net (code "296") (name "unconnected-(J7-Pad17)") (class "Default")
      (node (ref "J7") (pin "17") (pinfunction "17_17") (pintype "passive"))
    )
    (net (code "297") (name "unconnected-(J7-Pad18)") (class "Default")
      (node (ref "J7") (pin "18") (pinfunction "18_18") (pintype "passive"))
    )
    (net (code "298") (name "unconnected-(J7-Pad19)") (class "Default")
      (node (ref "J7") (pin "19") (pinfunction "19_19") (pintype "passive"))
    )
    (net (code "299") (name "unconnected-(J7-Pad20)") (class "Default")
      (node (ref "J7") (pin "20") (pinfunction "20_20") (pintype "passive"))
    )
    (net (code "300") (name "unconnected-(J7-Pad21)") (class "Default")
      (node (ref "J7") (pin "21") (pinfunction "21_21") (pintype "passive"))
    )
    (net (code "301") (name "unconnected-(J7-Pad22)") (class "Default")
      (node (ref "J7") (pin "22") (pinfunction "22_22") (pintype "passive"))
    )
    (net (code "302") (name "unconnected-(J7-Pad23)") (class "Default")
      (node (ref "J7") (pin "23") (pinfunction "23_23") (pintype "passive"))
    )
    (net (code "303") (name "unconnected-(J7-Pad24)") (class "Default")
      (node (ref "J7") (pin "24") (pinfunction "24_24") (pintype "passive"))
    )
    (net (code "304") (name "unconnected-(J8-Pad10)") (class "Default")
      (node (ref "J8") (pin "10") (pinfunction "10_10") (pintype "passive"))
    )
    (net (code "305") (name "unconnected-(J8-Pad12)") (class "Default")
      (node (ref "J8") (pin "12") (pinfunction "12_12") (pintype "passive"))
    )
    (net (code "306") (name "unconnected-(J8-Pad13)") (class "Default")
      (node (ref "J8") (pin "13") (pinfunction "13_13") (pintype "passive"))
    )
    (net (code "307") (name "unconnected-(J8-Pad14)") (class "Default")
      (node (ref "J8") (pin "14") (pinfunction "14_14") (pintype "passive"))
    )
    (net (code "308") (name "unconnected-(J8-Pad15)") (class "Default")
      (node (ref "J8") (pin "15") (pinfunction "15_15") (pintype "passive"))
    )
    (net (code "309") (name "unconnected-(J8-Pad16)") (class "Default")
      (node (ref "J8") (pin "16") (pinfunction "16_16") (pintype "passive"))
    )
    (net (code "310") (name "unconnected-(J8-Pad17)") (class "Default")
      (node (ref "J8") (pin "17") (pinfunction "17_17") (pintype "passive"))
    )
    (net (code "311") (name "unconnected-(J8-Pad18)") (class "Default")
      (node (ref "J8") (pin "18") (pinfunction "18_18") (pintype "passive"))
    )
    (net (code "312") (name "unconnected-(J8-Pad19)") (class "Default")
      (node (ref "J8") (pin "19") (pinfunction "19_19") (pintype "passive"))
    )
    (net (code "313") (name "unconnected-(J8-Pad20)") (class "Default")
      (node (ref "J8") (pin "20") (pinfunction "20_20") (pintype "passive"))
    )
    (net (code "314") (name "unconnected-(J8-Pad21)") (class "Default")
      (node (ref "J8") (pin "21") (pinfunction "21_21") (pintype "passive"))
    )
    (net (code "315") (name "unconnected-(J8-Pad22)") (class "Default")
      (node (ref "J8") (pin "22") (pinfunction "22_22") (pintype "passive"))
    )
    (net (code "316") (name "unconnected-(J8-Pad23)") (class "Default")
      (node (ref "J8") (pin "23") (pinfunction "23_23") (pintype "passive"))
    )
    (net (code "317") (name "unconnected-(J8-Pad24)") (class "Default")
      (node (ref "J8") (pin "24") (pinfunction "24_24") (pintype "passive"))
    )
    (net (code "318") (name "unconnected-(J9-Pad10)") (class "Default")
      (node (ref "J9") (pin "10") (pinfunction "10_10") (pintype "passive"))
    )
    (net (code "319") (name "unconnected-(J9-Pad12)") (class "Default")
      (node (ref "J9") (pin "12") (pinfunction "12_12") (pintype "passive"))
    )
    (net (code "320") (name "unconnected-(J9-Pad13)") (class "Default")
      (node (ref "J9") (pin "13") (pinfunction "13_13") (pintype "passive"))
    )
    (net (code "321") (name "unconnected-(J9-Pad14)") (class "Default")
      (node (ref "J9") (pin "14") (pinfunction "14_14") (pintype "passive"))
    )
    (net (code "322") (name "unconnected-(J9-Pad18)") (class "Default")
      (node (ref "J9") (pin "18") (pinfunction "18_18") (pintype "passive"))
    )
    (net (code "323") (name "unconnected-(J9-Pad19)") (class "Default")
      (node (ref "J9") (pin "19") (pinfunction "19_19") (pintype "passive"))
    )
    (net (code "324") (name "unconnected-(J9-Pad20)") (class "Default")
      (node (ref "J9") (pin "20") (pinfunction "20_20") (pintype "passive"))
    )
    (net (code "325") (name "unconnected-(J9-Pad21)") (class "Default")
      (node (ref "J9") (pin "21") (pinfunction "21_21") (pintype "passive"))
    )
    (net (code "326") (name "unconnected-(J9-Pad22)") (class "Default")
      (node (ref "J9") (pin "22") (pinfunction "22_22") (pintype "passive"))
    )
    (net (code "327") (name "unconnected-(J9-Pad23)") (class "Default")
      (node (ref "J9") (pin "23") (pinfunction "23_23") (pintype "passive"))
    )
    (net (code "328") (name "unconnected-(J9-Pad24)") (class "Default")
      (node (ref "J9") (pin "24") (pinfunction "24_24") (pintype "passive"))
    )
    (net (code "329") (name "unconnected-(J10-Pad10)") (class "Default")
      (node (ref "J10") (pin "10") (pinfunction "10_10") (pintype "passive"))
    )
    (net (code "330") (name "unconnected-(J10-Pad12)") (class "Default")
      (node (ref "J10") (pin "12") (pinfunction "12_12") (pintype "passive"))
    )
    (net (code "331") (name "unconnected-(J10-Pad13)") (class "Default")
      (node (ref "J10") (pin "13") (pinfunction "13_13") (pintype "passive"))
    )
    (net (code "332") (name "unconnected-(J10-Pad14)") (class "Default")
      (node (ref "J10") (pin "14") (pinfunction "14_14") (pintype "passive"))
    )
    (net (code "333") (name "unconnected-(J10-Pad15)") (class "Default")
      (node (ref "J10") (pin "15") (pinfunction "15_15") (pintype "passive"))
    )
    (net (code "334") (name "unconnected-(J10-Pad16)") (class "Default")
      (node (ref "J10") (pin "16") (pinfunction "16_16") (pintype "passive"))
    )
    (net (code "335") (name "unconnected-(J10-Pad17)") (class "Default")
      (node (ref "J10") (pin "17") (pinfunction "17_17") (pintype "passive"))
    )
    (net (code "336") (name "unconnected-(J10-Pad18)") (class "Default")
      (node (ref "J10") (pin "18") (pinfunction "18_18") (pintype "passive"))
    )
    (net (code "337") (name "unconnected-(J10-Pad19)") (class "Default")
      (node (ref "J10") (pin "19") (pinfunction "19_19") (pintype "passive"))
    )
    (net (code "338") (name "unconnected-(J10-Pad20)") (class "Default")
      (node (ref "J10") (pin "20") (pinfunction "20_20") (pintype "passive"))
    )
    (net (code "339") (name "unconnected-(J10-Pad21)") (class "Default")
      (node (ref "J10") (pin "21") (pinfunction "21_21") (pintype "passive"))
    )
    (net (code "340") (name "unconnected-(J10-Pad22)") (class "Default")
      (node (ref "J10") (pin "22") (pinfunction "22_22") (pintype "passive"))
    )
    (net (code "341") (name "unconnected-(J10-Pad23)") (class "Default")
      (node (ref "J10") (pin "23") (pinfunction "23_23") (pintype "passive"))
    )
    (net (code "342") (name "unconnected-(J10-Pad24)") (class "Default")
      (node (ref "J10") (pin "24") (pinfunction "24_24") (pintype "passive"))
    )
    (net (code "343") (name "unconnected-(J11-Pad10)") (class "Default")
      (node (ref "J11") (pin "10") (pinfunction "10_10") (pintype "passive"))
    )
    (net (code "344") (name "unconnected-(J11-Pad12)") (class "Default")
      (node (ref "J11") (pin "12") (pinfunction "12_12") (pintype "passive"))
    )
    (net (code "345") (name "unconnected-(J11-Pad13)") (class "Default")
      (node (ref "J11") (pin "13") (pinfunction "13_13") (pintype "passive"))
    )
    (net (code "346") (name "unconnected-(J11-Pad14)") (class "Default")
      (node (ref "J11") (pin "14") (pinfunction "14_14") (pintype "passive"))
    )
    (net (code "347") (name "unconnected-(J11-Pad15)") (class "Default")
      (node (ref "J11") (pin "15") (pinfunction "15_15") (pintype "passive"))
    )
    (net (code "348") (name "unconnected-(J11-Pad16)") (class "Default")
      (node (ref "J11") (pin "16") (pinfunction "16_16") (pintype "passive"))
    )
    (net (code "349") (name "unconnected-(J11-Pad17)") (class "Default")
      (node (ref "J11") (pin "17") (pinfunction "17_17") (pintype "passive"))
    )
    (net (code "350") (name "unconnected-(J11-Pad18)") (class "Default")
      (node (ref "J11") (pin "18") (pinfunction "18_18") (pintype "passive"))
    )
    (net (code "351") (name "unconnected-(J11-Pad19)") (class "Default")
      (node (ref "J11") (pin "19") (pinfunction "19_19") (pintype "passive"))
    )
    (net (code "352") (name "unconnected-(J11-Pad20)") (class "Default")
      (node (ref "J11") (pin "20") (pinfunction "20_20") (pintype "passive"))
    )
    (net (code "353") (name "unconnected-(J11-Pad21)") (class "Default")
      (node (ref "J11") (pin "21") (pinfunction "21_21") (pintype "passive"))
    )
    (net (code "354") (name "unconnected-(J11-Pad22)") (class "Default")
      (node (ref "J11") (pin "22") (pinfunction "22_22") (pintype "passive"))
    )
    (net (code "355") (name "unconnected-(J11-Pad23)") (class "Default")
      (node (ref "J11") (pin "23") (pinfunction "23_23") (pintype "passive"))
    )
    (net (code "356") (name "unconnected-(J11-Pad24)") (class "Default")
      (node (ref "J11") (pin "24") (pinfunction "24_24") (pintype "passive"))
    )
    (net (code "357") (name "unconnected-(J12-Pad10)") (class "Default")
      (node (ref "J12") (pin "10") (pinfunction "10_10") (pintype "passive"))
    )
    (net (code "358") (name "unconnected-(J12-Pad12)") (class "Default")
      (node (ref "J12") (pin "12") (pinfunction "12_12") (pintype "passive"))
    )
    (net (code "359") (name "unconnected-(J12-Pad13)") (class "Default")
      (node (ref "J12") (pin "13") (pinfunction "13_13") (pintype "passive"))
    )
    (net (code "360") (name "unconnected-(J12-Pad14)") (class "Default")
      (node (ref "J12") (pin "14") (pinfunction "14_14") (pintype "passive"))
    )
    (net (code "361") (name "unconnected-(J12-Pad18)") (class "Default")
      (node (ref "J12") (pin "18") (pinfunction "18_18") (pintype "passive"))
    )
    (net (code "362") (name "unconnected-(J12-Pad19)") (class "Default")
      (node (ref "J12") (pin "19") (pinfunction "19_19") (pintype "passive"))
    )
    (net (code "363") (name "unconnected-(J12-Pad20)") (class "Default")
      (node (ref "J12") (pin "20") (pinfunction "20_20") (pintype "passive"))
    )
    (net (code "364") (name "unconnected-(J12-Pad21)") (class "Default")
      (node (ref "J12") (pin "21") (pinfunction "21_21") (pintype "passive"))
    )
    (net (code "365") (name "unconnected-(J12-Pad22)") (class "Default")
      (node (ref "J12") (pin "22") (pinfunction "22_22") (pintype "passive"))
    )
    (net (code "366") (name "unconnected-(J12-Pad23)") (class "Default")
      (node (ref "J12") (pin "23") (pinfunction "23_23") (pintype "passive"))
    )
    (net (code "367") (name "unconnected-(J12-Pad24)") (class "Default")
      (node (ref "J12") (pin "24") (pinfunction "24_24") (pintype "passive"))
    )
    (net (code "368") (name "unconnected-(J13-Pad13)") (class "Default")
      (node (ref "J13") (pin "13") (pinfunction "13_13") (pintype "passive"))
    )
    (net (code "369") (name "unconnected-(J13-Pad14)") (class "Default")
      (node (ref "J13") (pin "14") (pinfunction "14_14") (pintype "passive"))
    )
    (net (code "370") (name "unconnected-(J13-Pad18)") (class "Default")
      (node (ref "J13") (pin "18") (pinfunction "18_18") (pintype "passive"))
    )
    (net (code "371") (name "unconnected-(J13-Pad19)") (class "Default")
      (node (ref "J13") (pin "19") (pinfunction "19_19") (pintype "passive"))
    )
    (net (code "372") (name "unconnected-(J13-Pad20)") (class "Default")
      (node (ref "J13") (pin "20") (pinfunction "20_20") (pintype "passive"))
    )
    (net (code "373") (name "unconnected-(J13-Pad21)") (class "Default")
      (node (ref "J13") (pin "21") (pinfunction "21_21") (pintype "passive"))
    )
    (net (code "374") (name "unconnected-(J13-Pad22)") (class "Default")
      (node (ref "J13") (pin "22") (pinfunction "22_22") (pintype "passive"))
    )
    (net (code "375") (name "unconnected-(J13-Pad23)") (class "Default")
      (node (ref "J13") (pin "23") (pinfunction "23_23") (pintype "passive"))
    )
    (net (code "376") (name "unconnected-(J13-Pad24)") (class "Default")
      (node (ref "J13") (pin "24") (pinfunction "24_24") (pintype "passive"))
    )
    (net (code "377") (name "unconnected-(J14-Pad13)") (class "Default")
      (node (ref "J14") (pin "13") (pinfunction "13_13") (pintype "passive"))
    )
    (net (code "378") (name "unconnected-(J14-Pad14)") (class "Default")
      (node (ref "J14") (pin "14") (pinfunction "14_14") (pintype "passive"))
    )
    (net (code "379") (name "unconnected-(J14-Pad18)") (class "Default")
      (node (ref "J14") (pin "18") (pinfunction "18_18") (pintype "passive"))
    )
    (net (code "380") (name "unconnected-(J14-Pad19)") (class "Default")
      (node (ref "J14") (pin "19") (pinfunction "19_19") (pintype "passive"))
    )
    (net (code "381") (name "unconnected-(J14-Pad20)") (class "Default")
      (node (ref "J14") (pin "20") (pinfunction "20_20") (pintype "passive"))
    )
    (net (code "382") (name "unconnected-(J14-Pad21)") (class "Default")
      (node (ref "J14") (pin "21") (pinfunction "21_21") (pintype "passive"))
    )
    (net (code "383") (name "unconnected-(J14-Pad22)") (class "Default")
      (node (ref "J14") (pin "22") (pinfunction "22_22") (pintype "passive"))
    )
    (net (code "384") (name "unconnected-(J14-Pad23)") (class "Default")
      (node (ref "J14") (pin "23") (pinfunction "23_23") (pintype "passive"))
    )
    (net (code "385") (name "unconnected-(J14-Pad24)") (class "Default")
      (node (ref "J14") (pin "24") (pinfunction "24_24") (pintype "passive"))
    )
    (net (code "386") (name "unconnected-(J15-Pad13)") (class "Default")
      (node (ref "J15") (pin "13") (pinfunction "13_13") (pintype "passive"))
    )
    (net (code "387") (name "unconnected-(J15-Pad14)") (class "Default")
      (node (ref "J15") (pin "14") (pinfunction "14_14") (pintype "passive"))
    )
    (net (code "388") (name "unconnected-(J15-Pad18)") (class "Default")
      (node (ref "J15") (pin "18") (pinfunction "18_18") (pintype "passive"))
    )
    (net (code "389") (name "unconnected-(J15-Pad19)") (class "Default")
      (node (ref "J15") (pin "19") (pinfunction "19_19") (pintype "passive"))
    )
    (net (code "390") (name "unconnected-(J15-Pad20)") (class "Default")
      (node (ref "J15") (pin "20") (pinfunction "20_20") (pintype "passive"))
    )
    (net (code "391") (name "unconnected-(J15-Pad21)") (class "Default")
      (node (ref "J15") (pin "21") (pinfunction "21_21") (pintype "passive"))
    )
    (net (code "392") (name "unconnected-(J15-Pad22)") (class "Default")
      (node (ref "J15") (pin "22") (pinfunction "22_22") (pintype "passive"))
    )
    (net (code "393") (name "unconnected-(J15-Pad23)") (class "Default")
      (node (ref "J15") (pin "23") (pinfunction "23_23") (pintype "passive"))
    )
    (net (code "394") (name "unconnected-(J15-Pad24)") (class "Default")
      (node (ref "J15") (pin "24") (pinfunction "24_24") (pintype "passive"))
    )
    (net (code "395") (name "unconnected-(J16-Pad13)") (class "Default")
      (node (ref "J16") (pin "13") (pinfunction "13_13") (pintype "passive"))
    )
    (net (code "396") (name "unconnected-(J16-Pad14)") (class "Default")
      (node (ref "J16") (pin "14") (pinfunction "14_14") (pintype "passive"))
    )
    (net (code "397") (name "unconnected-(J16-Pad18)") (class "Default")
      (node (ref "J16") (pin "18") (pinfunction "18_18") (pintype "passive"))
    )
    (net (code "398") (name "unconnected-(J16-Pad19)") (class "Default")
      (node (ref "J16") (pin "19") (pinfunction "19_19") (pintype "passive"))
    )
    (net (code "399") (name "unconnected-(J16-Pad20)") (class "Default")
      (node (ref "J16") (pin "20") (pinfunction "20_20") (pintype "passive"))
    )
    (net (code "400") (name "unconnected-(J16-Pad21)") (class "Default")
      (node (ref "J16") (pin "21") (pinfunction "21_21") (pintype "passive"))
    )
    (net (code "401") (name "unconnected-(J16-Pad22)") (class "Default")
      (node (ref "J16") (pin "22") (pinfunction "22_22") (pintype "passive"))
    )
    (net (code "402") (name "unconnected-(J16-Pad23)") (class "Default")
      (node (ref "J16") (pin "23") (pinfunction "23_23") (pintype "passive"))
    )
    (net (code "403") (name "unconnected-(J16-Pad24)") (class "Default")
      (node (ref "J16") (pin "24") (pinfunction "24_24") (pintype "passive"))
    )
    (net (code "404") (name "unconnected-(J17-Pad13)") (class "Default")
      (node (ref "J17") (pin "13") (pinfunction "13_13") (pintype "passive"))
    )
    (net (code "405") (name "unconnected-(J17-Pad14)") (class "Default")
      (node (ref "J17") (pin "14") (pinfunction "14_14") (pintype "passive"))
    )
    (net (code "406") (name "unconnected-(J17-Pad18)") (class "Default")
      (node (ref "J17") (pin "18") (pinfunction "18_18") (pintype "passive"))
    )
    (net (code "407") (name "unconnected-(J17-Pad19)") (class "Default")
      (node (ref "J17") (pin "19") (pinfunction "19_19") (pintype "passive"))
    )
    (net (code "408") (name "unconnected-(J17-Pad20)") (class "Default")
      (node (ref "J17") (pin "20") (pinfunction "20_20") (pintype "passive"))
    )
    (net (code "409") (name "unconnected-(J17-Pad21)") (class "Default")
      (node (ref "J17") (pin "21") (pinfunction "21_21") (pintype "passive"))
    )
    (net (code "410") (name "unconnected-(J17-Pad22)") (class "Default")
      (node (ref "J17") (pin "22") (pinfunction "22_22") (pintype "passive"))
    )
    (net (code "411") (name "unconnected-(J17-Pad23)") (class "Default")
      (node (ref "J17") (pin "23") (pinfunction "23_23") (pintype "passive"))
    )
    (net (code "412") (name "unconnected-(J17-Pad24)") (class "Default")
      (node (ref "J17") (pin "24") (pinfunction "24_24") (pintype "passive"))
    )
    (net (code "413") (name "unconnected-(J18-Pad13)") (class "Default")
      (node (ref "J18") (pin "13") (pinfunction "13_13") (pintype "passive"))
    )
    (net (code "414") (name "unconnected-(J18-Pad14)") (class "Default")
      (node (ref "J18") (pin "14") (pinfunction "14_14") (pintype "passive"))
    )
    (net (code "415") (name "unconnected-(J18-Pad18)") (class "Default")
      (node (ref "J18") (pin "18") (pinfunction "18_18") (pintype "passive"))
    )
    (net (code "416") (name "unconnected-(J18-Pad19)") (class "Default")
      (node (ref "J18") (pin "19") (pinfunction "19_19") (pintype "passive"))
    )
    (net (code "417") (name "unconnected-(J18-Pad20)") (class "Default")
      (node (ref "J18") (pin "20") (pinfunction "20_20") (pintype "passive"))
    )
    (net (code "418") (name "unconnected-(J18-Pad21)") (class "Default")
      (node (ref "J18") (pin "21") (pinfunction "21_21") (pintype "passive"))
    )
    (net (code "419") (name "unconnected-(J18-Pad22)") (class "Default")
      (node (ref "J18") (pin "22") (pinfunction "22_22") (pintype "passive"))
    )
    (net (code "420") (name "unconnected-(J18-Pad23)") (class "Default")
      (node (ref "J18") (pin "23") (pinfunction "23_23") (pintype "passive"))
    )
    (net (code "421") (name "unconnected-(J18-Pad24)") (class "Default")
      (node (ref "J18") (pin "24") (pinfunction "24_24") (pintype "passive"))
    )
    (net (code "422") (name "unconnected-(J19-Pad13)") (class "Default")
      (node (ref "J19") (pin "13") (pinfunction "13_13") (pintype "passive"))
    )
    (net (code "423") (name "unconnected-(J19-Pad14)") (class "Default")
      (node (ref "J19") (pin "14") (pinfunction "14_14") (pintype "passive"))
    )
    (net (code "424") (name "unconnected-(J19-Pad18)") (class "Default")
      (node (ref "J19") (pin "18") (pinfunction "18_18") (pintype "passive"))
    )
    (net (code "425") (name "unconnected-(J19-Pad19)") (class "Default")
      (node (ref "J19") (pin "19") (pinfunction "19_19") (pintype "passive"))
    )
    (net (code "426") (name "unconnected-(J19-Pad20)") (class "Default")
      (node (ref "J19") (pin "20") (pinfunction "20_20") (pintype "passive"))
    )
    (net (code "427") (name "unconnected-(J19-Pad21)") (class "Default")
      (node (ref "J19") (pin "21") (pinfunction "21_21") (pintype "passive"))
    )
    (net (code "428") (name "unconnected-(J19-Pad22)") (class "Default")
      (node (ref "J19") (pin "22") (pinfunction "22_22") (pintype "passive"))
    )
    (net (code "429") (name "unconnected-(J19-Pad23)") (class "Default")
      (node (ref "J19") (pin "23") (pinfunction "23_23") (pintype "passive"))
    )
    (net (code "430") (name "unconnected-(J19-Pad24)") (class "Default")
      (node (ref "J19") (pin "24") (pinfunction "24_24") (pintype "passive"))
    )
    (net (code "431") (name "unconnected-(J20-Pad13)") (class "Default")
      (node (ref "J20") (pin "13") (pinfunction "13_13") (pintype "passive"))
    )
    (net (code "432") (name "unconnected-(J20-Pad14)") (class "Default")
      (node (ref "J20") (pin "14") (pinfunction "14_14") (pintype "passive"))
    )
    (net (code "433") (name "unconnected-(J20-Pad18)") (class "Default")
      (node (ref "J20") (pin "18") (pinfunction "18_18") (pintype "passive"))
    )
    (net (code "434") (name "unconnected-(J20-Pad19)") (class "Default")
      (node (ref "J20") (pin "19") (pinfunction "19_19") (pintype "passive"))
    )
    (net (code "435") (name "unconnected-(J20-Pad20)") (class "Default")
      (node (ref "J20") (pin "20") (pinfunction "20_20") (pintype "passive"))
    )
    (net (code "436") (name "unconnected-(J20-Pad21)") (class "Default")
      (node (ref "J20") (pin "21") (pinfunction "21_21") (pintype "passive"))
    )
    (net (code "437") (name "unconnected-(J20-Pad22)") (class "Default")
      (node (ref "J20") (pin "22") (pinfunction "22_22") (pintype "passive"))
    )
    (net (code "438") (name "unconnected-(J20-Pad23)") (class "Default")
      (node (ref "J20") (pin "23") (pinfunction "23_23") (pintype "passive"))
    )
    (net (code "439") (name "unconnected-(J20-Pad24)") (class "Default")
      (node (ref "J20") (pin "24") (pinfunction "24_24") (pintype "passive"))
    )
    (net (code "440") (name "unconnected-(J21-Pad13)") (class "Default")
      (node (ref "J21") (pin "13") (pinfunction "13_13") (pintype "passive"))
    )
    (net (code "441") (name "unconnected-(J21-Pad14)") (class "Default")
      (node (ref "J21") (pin "14") (pinfunction "14_14") (pintype "passive"))
    )
    (net (code "442") (name "unconnected-(J21-Pad18)") (class "Default")
      (node (ref "J21") (pin "18") (pinfunction "18_18") (pintype "passive"))
    )
    (net (code "443") (name "unconnected-(J21-Pad19)") (class "Default")
      (node (ref "J21") (pin "19") (pinfunction "19_19") (pintype "passive"))
    )
    (net (code "444") (name "unconnected-(J21-Pad20)") (class "Default")
      (node (ref "J21") (pin "20") (pinfunction "20_20") (pintype "passive"))
    )
    (net (code "445") (name "unconnected-(J21-Pad21)") (class "Default")
      (node (ref "J21") (pin "21") (pinfunction "21_21") (pintype "passive"))
    )
    (net (code "446") (name "unconnected-(J21-Pad22)") (class "Default")
      (node (ref "J21") (pin "22") (pinfunction "22_22") (pintype "passive"))
    )
    (net (code "447") (name "unconnected-(J21-Pad23)") (class "Default")
      (node (ref "J21") (pin "23") (pinfunction "23_23") (pintype "passive"))
    )
    (net (code "448") (name "unconnected-(J21-Pad24)") (class "Default")
      (node (ref "J21") (pin "24") (pinfunction "24_24") (pintype "passive"))
    )
    (net (code "449") (name "unconnected-(J22-Pad13)") (class "Default")
      (node (ref "J22") (pin "13") (pinfunction "13_13") (pintype "passive"))
    )
    (net (code "450") (name "unconnected-(J22-Pad14)") (class "Default")
      (node (ref "J22") (pin "14") (pinfunction "14_14") (pintype "passive"))
    )
    (net (code "451") (name "unconnected-(J22-Pad18)") (class "Default")
      (node (ref "J22") (pin "18") (pinfunction "18_18") (pintype "passive"))
    )
    (net (code "452") (name "unconnected-(J22-Pad19)") (class "Default")
      (node (ref "J22") (pin "19") (pinfunction "19_19") (pintype "passive"))
    )
    (net (code "453") (name "unconnected-(J22-Pad20)") (class "Default")
      (node (ref "J22") (pin "20") (pinfunction "20_20") (pintype "passive"))
    )
    (net (code "454") (name "unconnected-(J22-Pad21)") (class "Default")
      (node (ref "J22") (pin "21") (pinfunction "21_21") (pintype "passive"))
    )
    (net (code "455") (name "unconnected-(J22-Pad22)") (class "Default")
      (node (ref "J22") (pin "22") (pinfunction "22_22") (pintype "passive"))
    )
    (net (code "456") (name "unconnected-(J22-Pad23)") (class "Default")
      (node (ref "J22") (pin "23") (pinfunction "23_23") (pintype "passive"))
    )
    (net (code "457") (name "unconnected-(J22-Pad24)") (class "Default")
      (node (ref "J22") (pin "24") (pinfunction "24_24") (pintype "passive"))
    )
  )
)
